# spi1_1.net
KiCad netlist of a schematic drawn in EAGLE
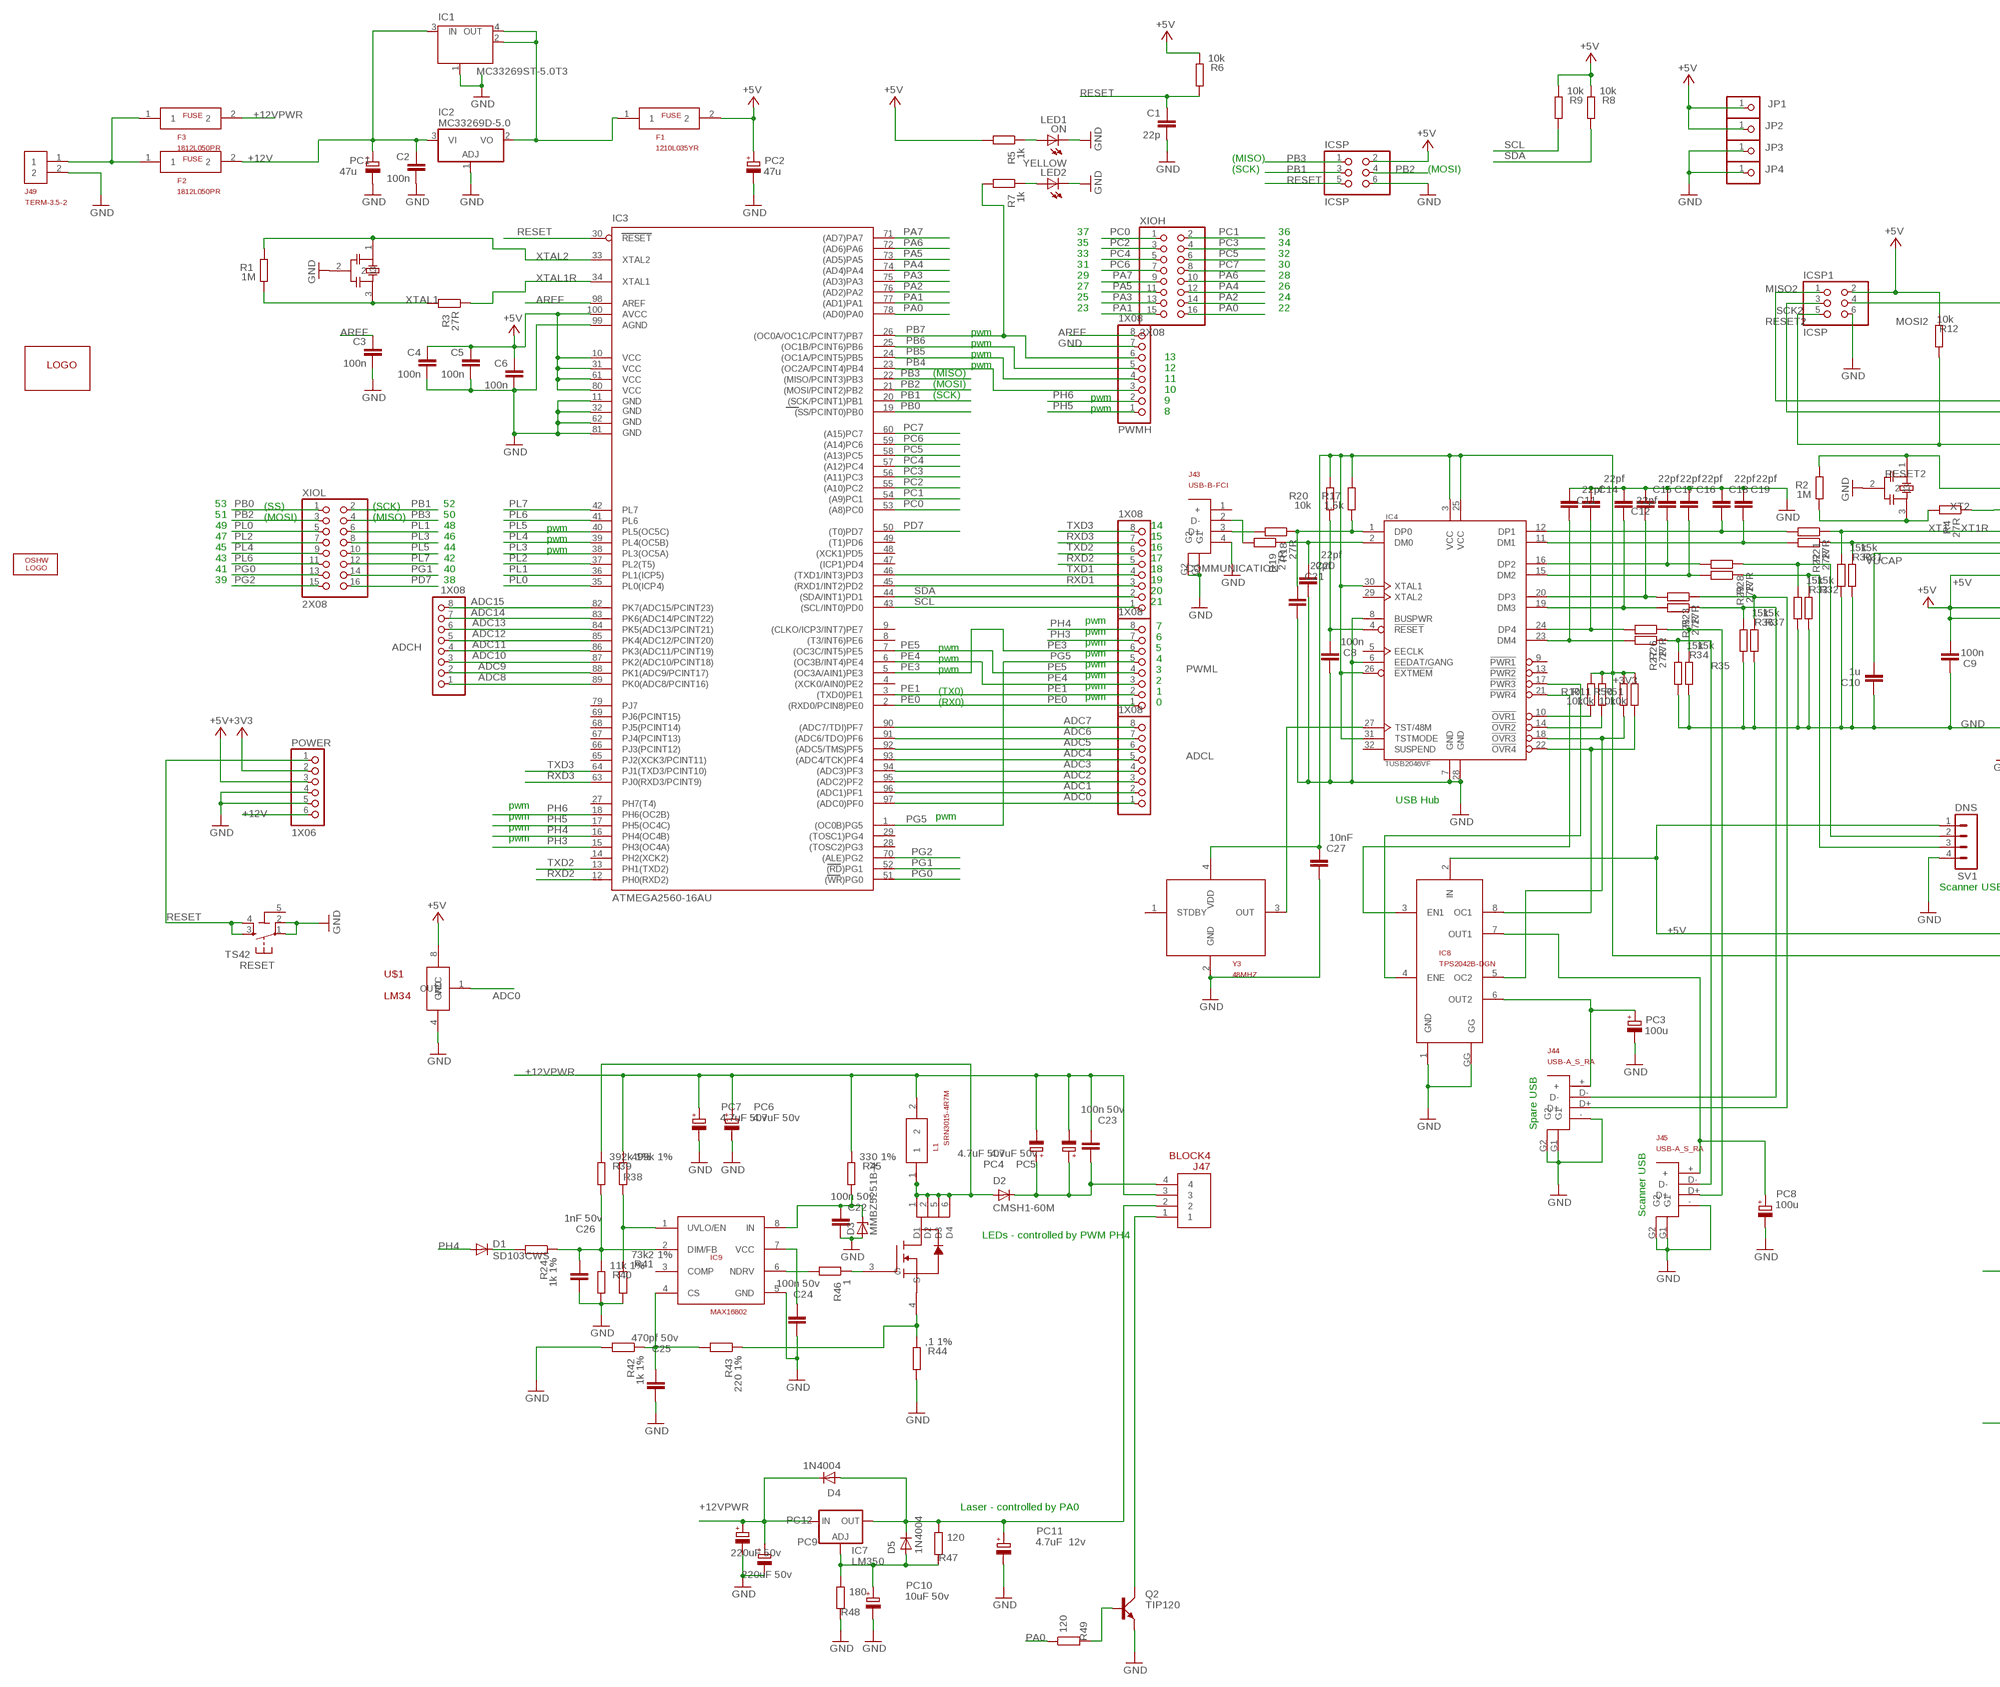
[diagram p0: schematic, sheet 1, part 1 of 2]
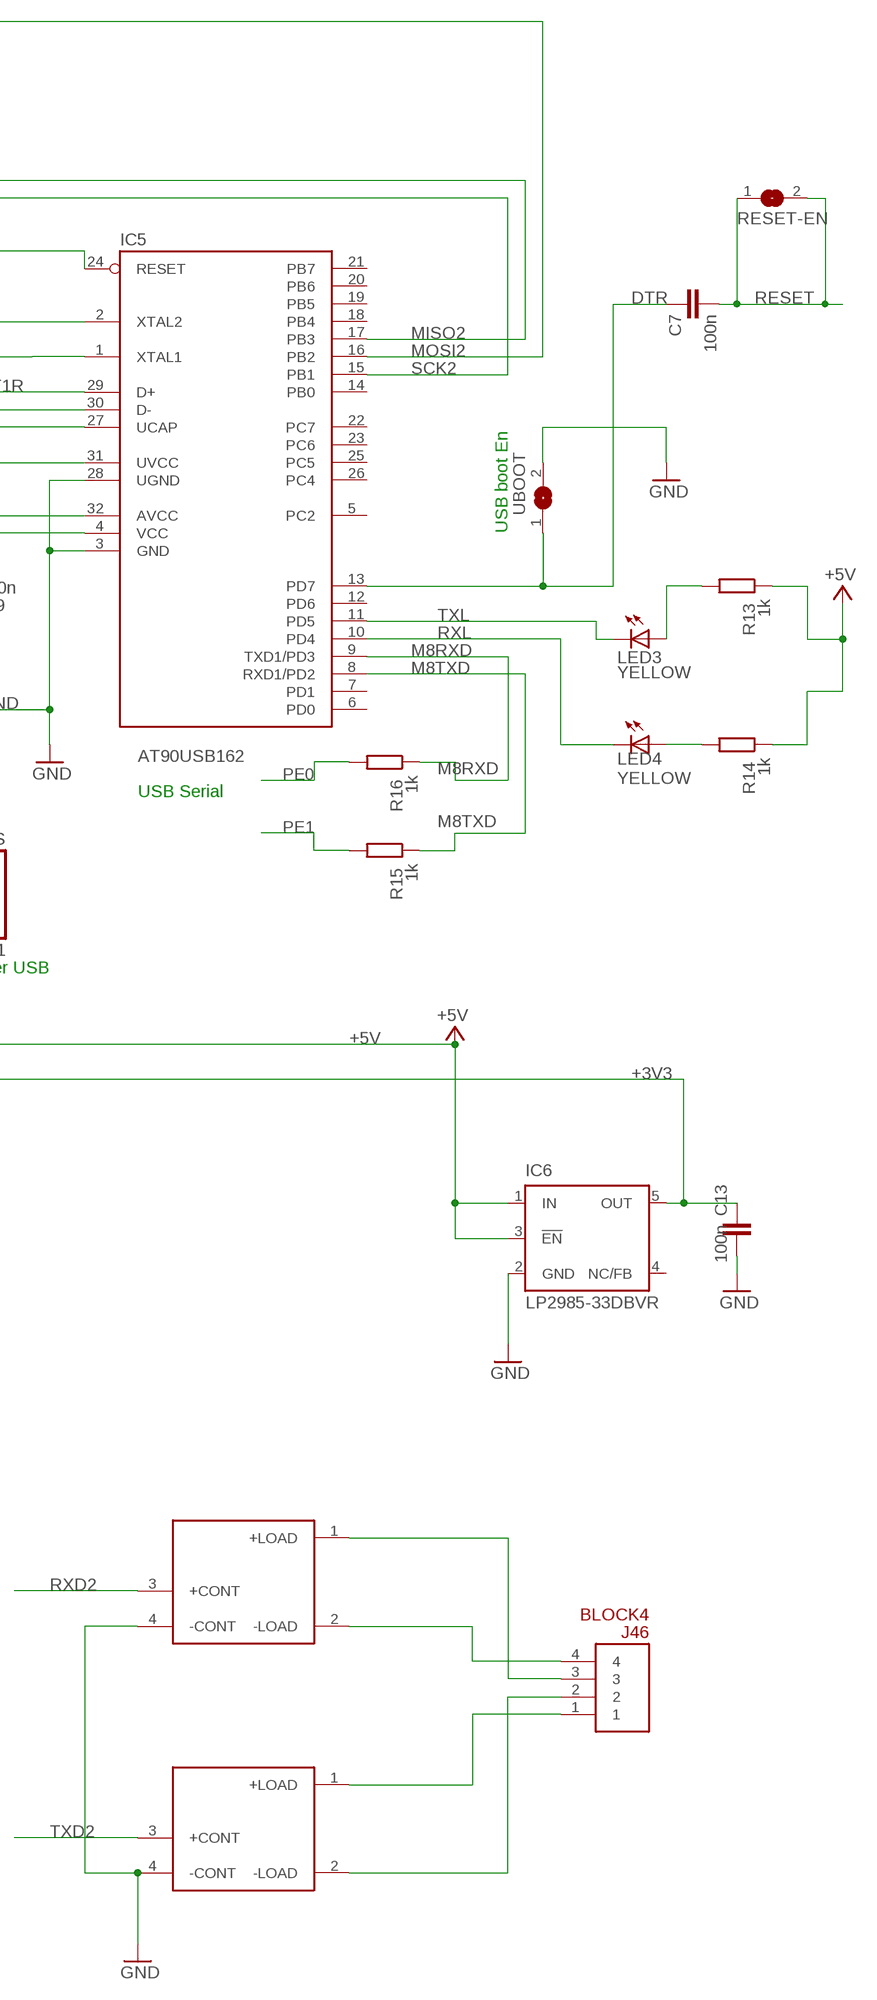
[diagram p1: schematic, sheet 1, part 2 of 2]

(export (version "E")
  (design (tool "Eeschema 10.0.6"))
  (components
    (comp (ref "ADCH")
      (value "1X08")
      (footprint "eagle-import:1X08")
      (libsource (lib "eagle-import") (part "PINHD-1X8"))
    )
    (comp (ref "ADCL")
      (value "1X08")
      (footprint "eagle-import:1X08")
      (libsource (lib "eagle-import") (part "PINHD-1X8"))
    )
    (comp (ref "C1")
      (value "22p")
      (footprint "eagle-import:C0603-ROUND")
      (libsource (lib "eagle-import") (part "C-EU0603-RND"))
    )
    (comp (ref "C2")
      (value "100n")
      (footprint "eagle-import:C0603-ROUND")
      (libsource (lib "eagle-import") (part "C-EU0603-RND"))
    )
    (comp (ref "C3")
      (value "100n")
      (footprint "eagle-import:C0603-ROUND")
      (libsource (lib "eagle-import") (part "C-EU0603-RND"))
    )
    (comp (ref "C4")
      (value "100n")
      (footprint "eagle-import:C0603-ROUND")
      (libsource (lib "eagle-import") (part "C-EU0603-RND"))
    )
    (comp (ref "C5")
      (value "100n")
      (footprint "eagle-import:C0603-ROUND")
      (libsource (lib "eagle-import") (part "C-EU0603-RND"))
    )
    (comp (ref "C6")
      (value "100n")
      (footprint "eagle-import:C0603-ROUND")
      (libsource (lib "eagle-import") (part "C-EU0603-RND"))
    )
    (comp (ref "C7")
      (value "100n")
      (footprint "eagle-import:C0603-ROUND")
      (libsource (lib "eagle-import") (part "C-EU0603-RND"))
    )
    (comp (ref "C8")
      (value "100n")
      (footprint "eagle-import:C0603-ROUND")
      (libsource (lib "eagle-import") (part "C-EU0603-RND"))
    )
    (comp (ref "C9")
      (value "100n")
      (footprint "eagle-import:C0603-ROUND")
      (libsource (lib "eagle-import") (part "C-EU0603-RND"))
    )
    (comp (ref "C10")
      (value "1u")
      (footprint "eagle-import:C0603-ROUND")
      (libsource (lib "eagle-import") (part "C-EU0603-RND"))
    )
    (comp (ref "C11")
      (value "22pf")
      (footprint "eagle-import:C0603-ROUND")
      (libsource (lib "eagle-import") (part "C-EU0603-RND"))
    )
    (comp (ref "C12")
      (value "22pf")
      (footprint "eagle-import:C0603-ROUND")
      (libsource (lib "eagle-import") (part "C-EU0603-RND"))
    )
    (comp (ref "C13")
      (value "100n")
      (footprint "eagle-import:C0603-ROUND")
      (libsource (lib "eagle-import") (part "C-EU0603-RND"))
    )
    (comp (ref "C14")
      (value "22pf")
      (footprint "eagle-import:C0603-ROUND")
      (libsource (lib "eagle-import") (part "C-EU0603-RND"))
    )
    (comp (ref "C15")
      (value "22pf")
      (footprint "eagle-import:C0603-ROUND")
      (libsource (lib "eagle-import") (part "C-EU0603-RND"))
    )
    (comp (ref "C16")
      (value "22pf")
      (footprint "eagle-import:C0603-ROUND")
      (libsource (lib "eagle-import") (part "C-EU0603-RND"))
    )
    (comp (ref "C17")
      (value "22pf")
      (footprint "eagle-import:C0603-ROUND")
      (libsource (lib "eagle-import") (part "C-EU0603-RND"))
    )
    (comp (ref "C18")
      (value "22pf")
      (footprint "eagle-import:C0603-ROUND")
      (libsource (lib "eagle-import") (part "C-EU0603-RND"))
    )
    (comp (ref "C19")
      (value "22pf")
      (footprint "eagle-import:C0603-ROUND")
      (libsource (lib "eagle-import") (part "C-EU0603-RND"))
    )
    (comp (ref "C20")
      (value "22pf")
      (footprint "eagle-import:C0603-ROUND")
      (libsource (lib "eagle-import") (part "C-EU0603-RND"))
    )
    (comp (ref "C21")
      (value "22pf")
      (footprint "eagle-import:C0603-ROUND")
      (libsource (lib "eagle-import") (part "C-EU0603-RND"))
    )
    (comp (ref "C22")
      (value "100n 50v")
      (footprint "eagle-import:C0603-ROUND")
      (libsource (lib "eagle-import") (part "C-EU0603-RND"))
    )
    (comp (ref "C23")
      (value "100n 50v")
      (footprint "eagle-import:C0603-ROUND")
      (libsource (lib "eagle-import") (part "C-EU0603-RND"))
    )
    (comp (ref "C24")
      (value "100n 50v")
      (footprint "eagle-import:C0603-ROUND")
      (libsource (lib "eagle-import") (part "C-EU0603-RND"))
    )
    (comp (ref "C25")
      (value "470pf 50v")
      (footprint "eagle-import:C0603-ROUND")
      (libsource (lib "eagle-import") (part "C-EU0603-RND"))
    )
    (comp (ref "C26")
      (value "1nF 50v")
      (footprint "eagle-import:C0603-ROUND")
      (libsource (lib "eagle-import") (part "C-EU0603-RND"))
    )
    (comp (ref "C27")
      (value "10nF")
      (footprint "eagle-import:C0603-ROUND")
      (libsource (lib "eagle-import") (part "C-EU0603-RND"))
    )
    (comp (ref "COMMUNICATION")
      (value "1X08")
      (footprint "eagle-import:1X08")
      (libsource (lib "eagle-import") (part "PINHD-1X8"))
    )
    (comp (ref "D1")
      (value "SD103CWS")
      (footprint "eagle-import:SOD323-W")
      (libsource (lib "eagle-import") (part "DIODE-SOD323-W"))
    )
    (comp (ref "D2")
      (value "CMSH1-60M")
      (footprint "eagle-import:SMA-DO214AC")
      (libsource (lib "eagle-import") (part "GF1"))
    )
    (comp (ref "D3")
      (value "MMBZ5251B-V")
      (footprint "eagle-import:SOT23")
      (libsource (lib "eagle-import") (part "ZENER-DIODESOT23"))
    )
    (comp (ref "D4")
      (value "1N4004")
      (footprint "eagle-import:SMA-DO214AC")
      (libsource (lib "eagle-import") (part "GF1"))
    )
    (comp (ref "D5")
      (value "1N4004")
      (footprint "eagle-import:SMA-DO214AC")
      (libsource (lib "eagle-import") (part "GF1"))
    )
    (comp (ref "F1")
      (value "1210L035YR")
      (footprint "eagle-import:POLY6")
      (libsource (lib "eagle-import") (part "1210L035YR"))
    )
    (comp (ref "F2")
      (value "1812L050PR")
      (footprint "eagle-import:POLY15")
      (libsource (lib "eagle-import") (part "1812L050PR"))
    )
    (comp (ref "F3")
      (value "1812L050PR")
      (footprint "eagle-import:POLY15")
      (libsource (lib "eagle-import") (part "1812L050PR"))
    )
    (comp (ref "IC1")
      (value "MC33269ST-5.0T3")
      (footprint "eagle-import:SOT223")
      (libsource (lib "eagle-import") (part "MC33269ST-3.3T3"))
    )
    (comp (ref "IC2")
      (value "MC33269D-5.0")
      (footprint "eagle-import:DPACK")
      (libsource (lib "eagle-import") (part "MC33269?D-5.0"))
    )
    (comp (ref "IC3")
      (value "ATMEGA2560-16AU")
      (footprint "eagle-import:TQFP100")
      (libsource (lib "eagle-import") (part "ATMEGAAU1280-16"))
    )
    (comp (ref "IC4")
      (value "TUSB2046VF")
      (footprint "eagle-import:TQFP32-08")
      (libsource (lib "eagle-import") (part "TUSB2046VF"))
    )
    (comp (ref "IC5")
      (value "AT90USB162")
      (footprint "eagle-import:TQFP32-08")
      (libsource (lib "eagle-import") (part "AT90USB162"))
    )
    (comp (ref "IC6")
      (value "LP2985-33DBVR")
      (footprint "eagle-import:SOT23-DBV")
      (fields (field (name "MF") "TEXAS INSTRUMENTS") (field (name "MPN") "TPS77033DBVT"))
      (libsource (lib "eagle-import") (part "TPS77033"))
    )
    (comp (ref "IC7")
      (value "LM350")
      (footprint "eagle-import:317TS")
      (libsource (lib "eagle-import") (part "LM317TS"))
    )
    (comp (ref "IC8")
      (value "TPS2042B-DGN")
      (footprint "eagle-import:DGN-8")
      (libsource (lib "eagle-import") (part "TPS2042B-DGN"))
    )
    (comp (ref "IC9")
      (value "MAX16802")
      (footprint "eagle-import:USOP-8")
      (libsource (lib "eagle-import") (part "MAX1602B"))
    )
    (comp (ref "ICSP")
      (value "ICSP")
      (footprint "eagle-import:2X03")
      (libsource (lib "eagle-import") (part "PINHD-2X3"))
    )
    (comp (ref "ICSP1")
      (value "ICSP")
      (footprint "eagle-import:2X03")
      (libsource (lib "eagle-import") (part "PINHD-2X3"))
    )
    (comp (ref "J43")
      (value "USB-B-FCI")
      (footprint "eagle-import:USB-B")
      (libsource (lib "eagle-import") (part "USB-B-FCI"))
    )
    (comp (ref "J44")
      (value "USB-A_S_RA")
      (footprint "eagle-import:USB-A")
      (libsource (lib "eagle-import") (part "USB-A_S_RA"))
    )
    (comp (ref "J45")
      (value "USB-A_S_RA")
      (footprint "eagle-import:USB-A")
      (libsource (lib "eagle-import") (part "USB-A_S_RA"))
    )
    (comp (ref "J46")
      (value "BLOCK4")
      (footprint "eagle-import:TERM3.5-4")
      (libsource (lib "eagle-import") (part "BLOCK4"))
    )
    (comp (ref "J47")
      (value "BLOCK4")
      (footprint "eagle-import:TERM3.5-4")
      (libsource (lib "eagle-import") (part "BLOCK4"))
    )
    (comp (ref "J49")
      (value "TERM-3.5-2")
      (footprint "eagle-import:TERM3.5-2")
      (libsource (lib "eagle-import") (part "TERM-3.5-2"))
    )
    (comp (ref "JP1")
      (value "PINHD-1X1")
      (footprint "eagle-import:1X01")
      (libsource (lib "eagle-import") (part "PINHD-1X1"))
    )
    (comp (ref "JP2")
      (value "PINHD-1X1")
      (footprint "eagle-import:1X01")
      (libsource (lib "eagle-import") (part "PINHD-1X1"))
    )
    (comp (ref "JP3")
      (value "PINHD-1X1")
      (footprint "eagle-import:1X01")
      (libsource (lib "eagle-import") (part "PINHD-1X1"))
    )
    (comp (ref "JP4")
      (value "PINHD-1X1")
      (footprint "eagle-import:1X01")
      (libsource (lib "eagle-import") (part "PINHD-1X1"))
    )
    (comp (ref "L1")
      (value "SRN3015-4R7M")
      (footprint "eagle-import:INDUCT1")
      (libsource (lib "eagle-import") (part "INDUCT1"))
    )
    (comp (ref "LED2")
      (value "YELLOW")
      (footprint "eagle-import:CHIP-LED0805")
      (libsource (lib "eagle-import") (part "LEDCHIP-LED0805"))
    )
    (comp (ref "LED3")
      (value "YELLOW")
      (footprint "eagle-import:CHIP-LED0805")
      (libsource (lib "eagle-import") (part "LEDCHIP-LED0805"))
    )
    (comp (ref "LED4")
      (value "YELLOW")
      (footprint "eagle-import:CHIP-LED0805")
      (libsource (lib "eagle-import") (part "LEDCHIP-LED0805"))
    )
    (comp (ref "LOGO2")
      (value "OSHW_LOGO_FILLX0350-NT")
      (footprint "eagle-import:OSHW_FILLX350_NOTEXT")
      (libsource (lib "eagle-import") (part "OSHW_LOGO_FILLX0350-NT"))
    )
    (comp (ref "ON")
      (value "LED1")
      (footprint "eagle-import:CHIP-LED0805")
      (libsource (lib "eagle-import") (part "LEDCHIP-LED0805"))
    )
    (comp (ref "PC1")
      (value "47u")
      (footprint "eagle-import:UD-6,3X7,7_NICHICON")
      (libsource (lib "eagle-import") (part "CPOL-EUUD-6,3X7,7"))
    )
    (comp (ref "PC2")
      (value "47u")
      (footprint "eagle-import:UD-6,3X7,7_NICHICON")
      (libsource (lib "eagle-import") (part "CPOL-EUUD-6,3X7,7"))
    )
    (comp (ref "PC3")
      (value "100u")
      (footprint "eagle-import:UD-6,3X7,7_NICHICON")
      (libsource (lib "eagle-import") (part "CPOL-EUUD-6,3X7,7"))
    )
    (comp (ref "PC4")
      (value "4.7uF 50v")
      (footprint "eagle-import:PANASONIC_C")
      (libsource (lib "eagle-import") (part "CPOL-EUC"))
    )
    (comp (ref "PC5")
      (value "4.7uF 50v")
      (footprint "eagle-import:PANASONIC_C")
      (libsource (lib "eagle-import") (part "CPOL-EUC"))
    )
    (comp (ref "PC6")
      (value "4.7uF 50v")
      (footprint "eagle-import:PANASONIC_C")
      (libsource (lib "eagle-import") (part "CPOL-EUC"))
    )
    (comp (ref "PC7")
      (value "4.7uF 50v")
      (footprint "eagle-import:PANASONIC_C")
      (libsource (lib "eagle-import") (part "CPOL-EUC"))
    )
    (comp (ref "PC8")
      (value "100u")
      (footprint "eagle-import:UD-6,3X7,7_NICHICON")
      (libsource (lib "eagle-import") (part "CPOL-EUUD-6,3X7,7"))
    )
    (comp (ref "PC9")
      (value "220uF 50v")
      (footprint "eagle-import:PANASONIC_G")
      (libsource (lib "eagle-import") (part "CPOL-EUG"))
    )
    (comp (ref "PC10")
      (value "10uF 50v")
      (footprint "eagle-import:PANASONIC_D")
      (libsource (lib "eagle-import") (part "CPOL-EUD"))
    )
    (comp (ref "PC11")
      (value "4.7uF 12v")
      (footprint "eagle-import:PANASONIC_C")
      (libsource (lib "eagle-import") (part "CPOL-EUC"))
    )
    (comp (ref "PC12")
      (value "220uF 50v")
      (footprint "eagle-import:PANASONIC_G")
      (libsource (lib "eagle-import") (part "CPOL-EUG"))
    )
    (comp (ref "POWER")
      (value "1X06")
      (footprint "eagle-import:1X06")
      (libsource (lib "eagle-import") (part "PINHD-1X6"))
    )
    (comp (ref "PWMH")
      (value "1X08")
      (footprint "eagle-import:1X08")
      (libsource (lib "eagle-import") (part "PINHD-1X8"))
    )
    (comp (ref "PWML")
      (value "1X08")
      (footprint "eagle-import:1X08")
      (libsource (lib "eagle-import") (part "PINHD-1X8"))
    )
    (comp (ref "Q2")
      (value "TIP120")
      (footprint "eagle-import:TO220AV")
      (libsource (lib "eagle-import") (part "TIP41C"))
    )
    (comp (ref "R1")
      (value "1M")
      (footprint "eagle-import:R0603-ROUND")
      (libsource (lib "eagle-import") (part "R-EU_R0603"))
    )
    (comp (ref "R2")
      (value "1M")
      (footprint "eagle-import:R0603-ROUND")
      (libsource (lib "eagle-import") (part "R-EU_R0603"))
    )
    (comp (ref "R3")
      (value "27R")
      (footprint "eagle-import:R0603-ROUND")
      (libsource (lib "eagle-import") (part "R-EU_R0603"))
    )
    (comp (ref "R4")
      (value "27R")
      (footprint "eagle-import:R0603-ROUND")
      (libsource (lib "eagle-import") (part "R-EU_R0603"))
    )
    (comp (ref "R5")
      (value "1k")
      (footprint "eagle-import:R0603-ROUND")
      (libsource (lib "eagle-import") (part "R-EU_R0603"))
    )
    (comp (ref "R6")
      (value "10k")
      (footprint "eagle-import:R0603-ROUND")
      (libsource (lib "eagle-import") (part "R-EU_R0603"))
    )
    (comp (ref "R7")
      (value "1k")
      (footprint "eagle-import:R0603-ROUND")
      (libsource (lib "eagle-import") (part "R-EU_R0603"))
    )
    (comp (ref "R8")
      (value "10k")
      (footprint "eagle-import:R0603-ROUND")
      (libsource (lib "eagle-import") (part "R-EU_R0603"))
    )
    (comp (ref "R9")
      (value "10k")
      (footprint "eagle-import:R0603-ROUND")
      (libsource (lib "eagle-import") (part "R-EU_R0603"))
    )
    (comp (ref "R10")
      (value "10k")
      (footprint "eagle-import:R0603-ROUND")
      (libsource (lib "eagle-import") (part "R-EU_R0603"))
    )
    (comp (ref "R11")
      (value "10k")
      (footprint "eagle-import:R0603-ROUND")
      (libsource (lib "eagle-import") (part "R-EU_R0603"))
    )
    (comp (ref "R12")
      (value "10k")
      (footprint "eagle-import:R0603-ROUND")
      (libsource (lib "eagle-import") (part "R-EU_R0603"))
    )
    (comp (ref "R13")
      (value "1k")
      (footprint "eagle-import:R0603-ROUND")
      (libsource (lib "eagle-import") (part "R-EU_R0603"))
    )
    (comp (ref "R14")
      (value "1k")
      (footprint "eagle-import:R0603-ROUND")
      (libsource (lib "eagle-import") (part "R-EU_R0603"))
    )
    (comp (ref "R15")
      (value "1k")
      (footprint "eagle-import:R0603-ROUND")
      (libsource (lib "eagle-import") (part "R-EU_R0603"))
    )
    (comp (ref "R16")
      (value "1k")
      (footprint "eagle-import:R0603-ROUND")
      (libsource (lib "eagle-import") (part "R-EU_R0603"))
    )
    (comp (ref "R17")
      (value "1.5k")
      (footprint "eagle-import:R0603-ROUND")
      (libsource (lib "eagle-import") (part "R-EU_R0603"))
    )
    (comp (ref "R18")
      (value "27R")
      (footprint "eagle-import:R0603-ROUND")
      (libsource (lib "eagle-import") (part "R-EU_R0603"))
    )
    (comp (ref "R19")
      (value "27R")
      (footprint "eagle-import:R0603-ROUND")
      (libsource (lib "eagle-import") (part "R-EU_R0603"))
    )
    (comp (ref "R20")
      (value "10k")
      (footprint "eagle-import:R0603-ROUND")
      (libsource (lib "eagle-import") (part "R-EU_R0603"))
    )
    (comp (ref "R21")
      (value "27R")
      (footprint "eagle-import:R0603-ROUND")
      (libsource (lib "eagle-import") (part "R-EU_R0603"))
    )
    (comp (ref "R22")
      (value "27R")
      (footprint "eagle-import:R0603-ROUND")
      (libsource (lib "eagle-import") (part "R-EU_R0603"))
    )
    (comp (ref "R23")
      (value "27R")
      (footprint "eagle-import:R0603-ROUND")
      (libsource (lib "eagle-import") (part "R-EU_R0603"))
    )
    (comp (ref "R24")
      (value "1k 1%")
      (footprint "eagle-import:R0603-ROUND")
      (libsource (lib "eagle-import") (part "R-EU_R0603"))
    )
    (comp (ref "R25")
      (value "27R")
      (footprint "eagle-import:R0603-ROUND")
      (libsource (lib "eagle-import") (part "R-EU_R0603"))
    )
    (comp (ref "R26")
      (value "27R")
      (footprint "eagle-import:R0603-ROUND")
      (libsource (lib "eagle-import") (part "R-EU_R0603"))
    )
    (comp (ref "R27")
      (value "27R")
      (footprint "eagle-import:R0603-ROUND")
      (libsource (lib "eagle-import") (part "R-EU_R0603"))
    )
    (comp (ref "R28")
      (value "27R")
      (footprint "eagle-import:R0603-ROUND")
      (libsource (lib "eagle-import") (part "R-EU_R0603"))
    )
    (comp (ref "R29")
      (value "27R")
      (footprint "eagle-import:R0603-ROUND")
      (libsource (lib "eagle-import") (part "R-EU_R0603"))
    )
    (comp (ref "R30")
      (value "15k")
      (footprint "eagle-import:R0603-ROUND")
      (libsource (lib "eagle-import") (part "R-EU_R0603"))
    )
    (comp (ref "R31")
      (value "15k")
      (footprint "eagle-import:R0603-ROUND")
      (libsource (lib "eagle-import") (part "R-EU_R0603"))
    )
    (comp (ref "R32")
      (value "15k")
      (footprint "eagle-import:R0603-ROUND")
      (libsource (lib "eagle-import") (part "R-EU_R0603"))
    )
    (comp (ref "R33")
      (value "15k")
      (footprint "eagle-import:R0603-ROUND")
      (libsource (lib "eagle-import") (part "R-EU_R0603"))
    )
    (comp (ref "R34")
      (value "15k")
      (footprint "eagle-import:R0603-ROUND")
      (libsource (lib "eagle-import") (part "R-EU_R0603"))
    )
    (comp (ref "R35")
      (value "15k")
      (footprint "eagle-import:R0603-ROUND")
      (libsource (lib "eagle-import") (part "R-EU_R0603"))
    )
    (comp (ref "R36")
      (value "15k")
      (footprint "eagle-import:R0603-ROUND")
      (libsource (lib "eagle-import") (part "R-EU_R0603"))
    )
    (comp (ref "R37")
      (value "15k")
      (footprint "eagle-import:R0603-ROUND")
      (libsource (lib "eagle-import") (part "R-EU_R0603"))
    )
    (comp (ref "R38")
      (value "499k 1%")
      (footprint "eagle-import:R0603-ROUND")
      (libsource (lib "eagle-import") (part "R-EU_R0603"))
    )
    (comp (ref "R39")
      (value "392k 1%")
      (footprint "eagle-import:R0603-ROUND")
      (libsource (lib "eagle-import") (part "R-EU_R0603"))
    )
    (comp (ref "R40")
      (value "11k 1%")
      (footprint "eagle-import:R0603-ROUND")
      (libsource (lib "eagle-import") (part "R-EU_R0603"))
    )
    (comp (ref "R41")
      (value "73k2 1%")
      (footprint "eagle-import:R0603-ROUND")
      (libsource (lib "eagle-import") (part "R-EU_R0603"))
    )
    (comp (ref "R42")
      (value "1k 1%")
      (footprint "eagle-import:R0603-ROUND")
      (libsource (lib "eagle-import") (part "R-EU_R0603"))
    )
    (comp (ref "R43")
      (value "220 1%")
      (footprint "eagle-import:R0603-ROUND")
      (libsource (lib "eagle-import") (part "R-EU_R0603"))
    )
    (comp (ref "R44")
      (value ",1 1%")
      (footprint "eagle-import:R1206")
      (libsource (lib "eagle-import") (part "R-EU_R1206"))
    )
    (comp (ref "R45")
      (value "330 1%")
      (footprint "eagle-import:R1206")
      (libsource (lib "eagle-import") (part "R-EU_R1206"))
    )
    (comp (ref "R46")
      (value "1")
      (footprint "eagle-import:R0603-ROUND")
      (libsource (lib "eagle-import") (part "R-EU_R0603"))
    )
    (comp (ref "R47")
      (value "120")
      (footprint "eagle-import:R0603-ROUND")
      (libsource (lib "eagle-import") (part "R-EU_R0603"))
    )
    (comp (ref "R48")
      (value "180")
      (footprint "eagle-import:R0603-ROUND")
      (libsource (lib "eagle-import") (part "R-EU_R0603"))
    )
    (comp (ref "R49")
      (value "120")
      (footprint "eagle-import:R0603-ROUND")
      (libsource (lib "eagle-import") (part "R-EU_R0603"))
    )
    (comp (ref "R50")
      (value "10k")
      (footprint "eagle-import:R0603-ROUND")
      (libsource (lib "eagle-import") (part "R-EU_R0603"))
    )
    (comp (ref "R51")
      (value "10k")
      (footprint "eagle-import:R0603-ROUND")
      (libsource (lib "eagle-import") (part "R-EU_R0603"))
    )
    (comp (ref "RELAY1")
      (value "XRELAY")
      (footprint "eagle-import:XRELAY")
      (libsource (lib "eagle-import") (part "XRELAY"))
    )
    (comp (ref "RELAY2")
      (value "XRELAY")
      (footprint "eagle-import:XRELAY")
      (libsource (lib "eagle-import") (part "XRELAY"))
    )
    (comp (ref "RESET")
      (value "TS42")
      (footprint "eagle-import:TS42")
      (libsource (lib "eagle-import") (part "TS42"))
    )
    (comp (ref "RESET-EN")
      (value "SJ")
      (footprint "eagle-import:SJ")
      (libsource (lib "eagle-import") (part "SJ"))
    )
    (comp (ref "SV1")
      (value "DNS")
      (footprint "eagle-import:MA04-1")
      (libsource (lib "eagle-import") (part "MA04-1"))
    )
    (comp (ref "U$1")
      (value "LM34")
      (footprint "eagle-import:SS08")
      (libsource (lib "eagle-import") (part "LM34"))
    )
    (comp (ref "U$6")
      (value "SI3458DVB")
      (footprint "eagle-import:TSOP6")
      (libsource (lib "eagle-import") (part "SI3458DVB"))
    )
    (comp (ref "U$15")
      (value "LOGO")
      (footprint "eagle-import:LOGO")
      (libsource (lib "eagle-import") (part "LOGO"))
    )
    (comp (ref "UBOOT")
      (value "SJ")
      (footprint "eagle-import:SJ")
      (libsource (lib "eagle-import") (part "SJ"))
    )
    (comp (ref "XIOH")
      (value "2X08")
      (footprint "eagle-import:2X08")
      (libsource (lib "eagle-import") (part "PINHD-2X8"))
    )
    (comp (ref "XIOL")
      (value "2X08")
      (footprint "eagle-import:2X08")
      (libsource (lib "eagle-import") (part "PINHD-2X8"))
    )
    (comp (ref "Y1")
      (value "AWSCR")
      (footprint "eagle-import:RESONATOR1")
      (libsource (lib "eagle-import") (part "AWSCR"))
    )
    (comp (ref "Y2")
      (value "AWSCR")
      (footprint "eagle-import:RESONATOR1")
      (libsource (lib "eagle-import") (part "AWSCR"))
    )
    (comp (ref "Y3")
      (value "48MHZ")
      (footprint "eagle-import:XTAL1")
      (libsource (lib "eagle-import") (part "XTAL1"))
    )
  )
  (nets
    (net (code "1") (name "+3V3") (class "Default")
      (node (ref "C13") (pin "2") (pinfunction "2_2") (pintype "passive"))
      (node (ref "C27") (pin "1") (pinfunction "1_1") (pintype "passive"))
      (node (ref "IC4") (pin "25") (pinfunction "VCC_25") (pintype "power_in"))
      (node (ref "IC4") (pin "26") (pinfunction "~{EXTMEM}_26") (pintype "bidirectional"))
      (node (ref "IC4") (pin "3") (pinfunction "VCC_3") (pintype "power_in"))
      (node (ref "IC4") (pin "30") (pinfunction "XTAL1_30") (pintype "bidirectional"))
      (node (ref "IC4") (pin "31") (pinfunction "TSTMODE_31") (pintype "input"))
      (node (ref "IC6") (pin "5") (pinfunction "OUT_5") (pintype "passive"))
      (node (ref "POWER") (pin "2") (pinfunction "2_2") (pintype "passive"))
      (node (ref "R10") (pin "2") (pinfunction "2_2") (pintype "passive"))
      (node (ref "R11") (pin "2") (pinfunction "2_2") (pintype "passive"))
      (node (ref "R17") (pin "2") (pinfunction "2_2") (pintype "passive"))
      (node (ref "R20") (pin "2") (pinfunction "2_2") (pintype "passive"))
      (node (ref "R50") (pin "2") (pinfunction "2_2") (pintype "passive"))
      (node (ref "R51") (pin "2") (pinfunction "2_2") (pintype "passive"))
      (node (ref "Y3") (pin "4") (pinfunction "VDD_4") (pintype "bidirectional"))
    )
    (net (code "2") (name "+5V") (class "Default")
      (node (ref "C4") (pin "1") (pinfunction "1_1") (pintype "passive"))
      (node (ref "C5") (pin "1") (pinfunction "1_1") (pintype "passive"))
      (node (ref "C6") (pin "1") (pinfunction "1_1") (pintype "passive"))
      (node (ref "C9") (pin "1") (pinfunction "1_1") (pintype "passive"))
      (node (ref "F1") (pin "2") (pinfunction "2_2") (pintype "bidirectional"))
      (node (ref "IC3") (pin "10") (pinfunction "VCC_10") (pintype "power_in"))
      (node (ref "IC3") (pin "100") (pinfunction "AVCC_100") (pintype "power_in"))
      (node (ref "IC3") (pin "31") (pinfunction "VCC1_31") (pintype "power_in"))
      (node (ref "IC3") (pin "61") (pinfunction "VCC2_61") (pintype "power_in"))
      (node (ref "IC3") (pin "80") (pinfunction "VCC3_80") (pintype "power_in"))
      (node (ref "IC5") (pin "31") (pinfunction "UVCC_31") (pintype "power_in"))
      (node (ref "IC5") (pin "32") (pinfunction "AVCC_32") (pintype "bidirectional"))
      (node (ref "IC5") (pin "4") (pinfunction "VCC_4") (pintype "bidirectional"))
      (node (ref "IC6") (pin "1") (pinfunction "IN_1") (pintype "input"))
      (node (ref "IC6") (pin "3") (pinfunction "~{EN}_3") (pintype "input"))
      (node (ref "IC8") (pin "2") (pinfunction "IN_2") (pintype "bidirectional"))
      (node (ref "ICSP") (pin "2") (pinfunction "2_2") (pintype "passive"))
      (node (ref "ICSP1") (pin "2") (pinfunction "2_2") (pintype "passive"))
      (node (ref "JP1") (pin "1") (pinfunction "1_1") (pintype "passive"))
      (node (ref "JP2") (pin "1") (pinfunction "1_1") (pintype "passive"))
      (node (ref "PC2") (pin "+") (pinfunction "+_+") (pintype "passive"))
      (node (ref "POWER") (pin "3") (pinfunction "3_3") (pintype "passive"))
      (node (ref "R12") (pin "1") (pinfunction "1_1") (pintype "passive"))
      (node (ref "R13") (pin "1") (pinfunction "1_1") (pintype "passive"))
      (node (ref "R14") (pin "1") (pinfunction "1_1") (pintype "passive"))
      (node (ref "R5") (pin "2") (pinfunction "2_2") (pintype "passive"))
      (node (ref "R6") (pin "1") (pinfunction "1_1") (pintype "passive"))
      (node (ref "R8") (pin "1") (pinfunction "1_1") (pintype "passive"))
      (node (ref "R9") (pin "1") (pinfunction "1_1") (pintype "passive"))
      (node (ref "SV1") (pin "1") (pinfunction "1_1") (pintype "passive"))
      (node (ref "U$1") (pin "8") (pinfunction "VCC_8") (pintype "bidirectional"))
    )
    (net (code "3") (name "/+12V") (class "Default")
      (node (ref "C2") (pin "1") (pinfunction "1_1") (pintype "passive"))
      (node (ref "F2") (pin "2") (pinfunction "2_2") (pintype "bidirectional"))
      (node (ref "IC1") (pin "3") (pinfunction "IN_3") (pintype "input"))
      (node (ref "IC2") (pin "3") (pinfunction "VI_3") (pintype "input"))
      (node (ref "PC1") (pin "+") (pinfunction "+_+") (pintype "passive"))
      (node (ref "POWER") (pin "6") (pinfunction "6_6") (pintype "passive"))
    )
    (net (code "4") (name "/+12VPWR") (class "Default")
      (node (ref "C23") (pin "1") (pinfunction "1_1") (pintype "passive"))
      (node (ref "D4") (pin "K") (pinfunction "C_K") (pintype "passive"))
      (node (ref "F3") (pin "2") (pinfunction "2_2") (pintype "bidirectional"))
      (node (ref "IC7") (pin "3") (pinfunction "IN_3") (pintype "input"))
      (node (ref "J47") (pin "3") (pinfunction "3_3") (pintype "bidirectional"))
      (node (ref "L1") (pin "2") (pinfunction "2_2") (pintype "bidirectional"))
      (node (ref "PC12") (pin "+") (pinfunction "+_+") (pintype "passive"))
      (node (ref "PC4") (pin "-") (pinfunction "-_-") (pintype "passive"))
      (node (ref "PC5") (pin "-") (pinfunction "-_-") (pintype "passive"))
      (node (ref "PC6") (pin "+") (pinfunction "+_+") (pintype "passive"))
      (node (ref "PC7") (pin "+") (pinfunction "+_+") (pintype "passive"))
      (node (ref "PC9") (pin "+") (pinfunction "+_+") (pintype "passive"))
      (node (ref "R38") (pin "1") (pinfunction "1_1") (pintype "passive"))
      (node (ref "R45") (pin "1") (pinfunction "1_1") (pintype "passive"))
    )
    (net (code "5") (name "/5-GND") (class "Default")
      (node (ref "RESET") (pin "5") (pinfunction "5-GND_5") (pintype "power_in"))
    )
    (net (code "6") (name "/ADC0") (class "Default")
      (node (ref "ADCL") (pin "1") (pinfunction "1_1") (pintype "passive"))
      (node (ref "IC3") (pin "97") (pinfunction "(ADC0)PF0_97") (pintype "bidirectional"))
      (node (ref "U$1") (pin "1") (pinfunction "OUT_1") (pintype "bidirectional"))
    )
    (net (code "7") (name "/ADC1") (class "Default")
      (node (ref "ADCL") (pin "2") (pinfunction "2_2") (pintype "passive"))
      (node (ref "IC3") (pin "96") (pinfunction "(ADC1)PF1_96") (pintype "bidirectional"))
    )
    (net (code "8") (name "/ADC2") (class "Default")
      (node (ref "ADCL") (pin "3") (pinfunction "3_3") (pintype "passive"))
      (node (ref "IC3") (pin "95") (pinfunction "(ADC2)PF2_95") (pintype "bidirectional"))
    )
    (net (code "9") (name "/ADC3") (class "Default")
      (node (ref "ADCL") (pin "4") (pinfunction "4_4") (pintype "passive"))
      (node (ref "IC3") (pin "94") (pinfunction "(ADC3)PF3_94") (pintype "bidirectional"))
    )
    (net (code "10") (name "/ADC4") (class "Default")
      (node (ref "ADCL") (pin "5") (pinfunction "5_5") (pintype "passive"))
      (node (ref "IC3") (pin "93") (pinfunction "(ADC4/TCK)PF4_93") (pintype "bidirectional"))
    )
    (net (code "11") (name "/ADC5") (class "Default")
      (node (ref "ADCL") (pin "6") (pinfunction "6_6") (pintype "passive"))
      (node (ref "IC3") (pin "92") (pinfunction "(ADC5/TMS)PF5_92") (pintype "bidirectional"))
    )
    (net (code "12") (name "/ADC6") (class "Default")
      (node (ref "ADCL") (pin "7") (pinfunction "7_7") (pintype "passive"))
      (node (ref "IC3") (pin "91") (pinfunction "(ADC6/TDO)PF6_91") (pintype "bidirectional"))
    )
    (net (code "13") (name "/ADC7") (class "Default")
      (node (ref "ADCL") (pin "8") (pinfunction "8_8") (pintype "passive"))
      (node (ref "IC3") (pin "90") (pinfunction "(ADC7/TDI)PF7_90") (pintype "bidirectional"))
    )
    (net (code "14") (name "/ADC8") (class "Default")
      (node (ref "ADCH") (pin "1") (pinfunction "1_1") (pintype "passive"))
      (node (ref "IC3") (pin "89") (pinfunction "PK0(ADC8/PCINT16)_89") (pintype "bidirectional"))
    )
    (net (code "15") (name "/ADC9") (class "Default")
      (node (ref "ADCH") (pin "2") (pinfunction "2_2") (pintype "passive"))
      (node (ref "IC3") (pin "88") (pinfunction "PK1(ADC9/PCINT17)_88") (pintype "bidirectional"))
    )
    (net (code "16") (name "/ADC10") (class "Default")
      (node (ref "ADCH") (pin "3") (pinfunction "3_3") (pintype "passive"))
      (node (ref "IC3") (pin "87") (pinfunction "PK2(ADC10/PCINT18)_87") (pintype "bidirectional"))
    )
    (net (code "17") (name "/ADC11") (class "Default")
      (node (ref "ADCH") (pin "4") (pinfunction "4_4") (pintype "passive"))
      (node (ref "IC3") (pin "86") (pinfunction "PK3(ADC11/PCINT19)_86") (pintype "bidirectional"))
    )
    (net (code "18") (name "/ADC12") (class "Default")
      (node (ref "ADCH") (pin "5") (pinfunction "5_5") (pintype "passive"))
      (node (ref "IC3") (pin "85") (pinfunction "PK4(ADC12/PCINT20)_85") (pintype "bidirectional"))
    )
    (net (code "19") (name "/ADC13") (class "Default")
      (node (ref "ADCH") (pin "6") (pinfunction "6_6") (pintype "passive"))
      (node (ref "IC3") (pin "84") (pinfunction "PK5(ADC13/PCINT21)_84") (pintype "bidirectional"))
    )
    (net (code "20") (name "/ADC14") (class "Default")
      (node (ref "ADCH") (pin "7") (pinfunction "7_7") (pintype "passive"))
      (node (ref "IC3") (pin "83") (pinfunction "PK6(ADC14/PCINT22)_83") (pintype "bidirectional"))
    )
    (net (code "21") (name "/ADC15") (class "Default")
      (node (ref "ADCH") (pin "8") (pinfunction "8_8") (pintype "passive"))
      (node (ref "IC3") (pin "82") (pinfunction "PK7(ADC15/PCINT23)_82") (pintype "bidirectional"))
    )
    (net (code "22") (name "/AREF") (class "Default")
      (node (ref "C3") (pin "1") (pinfunction "1_1") (pintype "passive"))
      (node (ref "IC3") (pin "98") (pinfunction "AREF_98") (pintype "bidirectional"))
      (node (ref "PWMH") (pin "8") (pinfunction "8_8") (pintype "passive"))
    )
    (net (code "23") (name "/DTR") (class "Default")
      (node (ref "C7") (pin "1") (pinfunction "1_1") (pintype "passive"))
      (node (ref "IC5") (pin "13") (pinfunction "PD7_13") (pintype "bidirectional"))
      (node (ref "UBOOT") (pin "1") (pinfunction "1_1") (pintype "passive"))
    )
    (net (code "24") (name "/M8RXD") (class "Default")
      (node (ref "IC5") (pin "9") (pinfunction "TXD1/PD3_9") (pintype "bidirectional"))
      (node (ref "R16") (pin "1") (pinfunction "1_1") (pintype "passive"))
    )
    (net (code "25") (name "/M8TXD") (class "Default")
      (node (ref "IC5") (pin "8") (pinfunction "RXD1/PD2_8") (pintype "bidirectional"))
      (node (ref "R15") (pin "1") (pinfunction "1_1") (pintype "passive"))
    )
    (net (code "26") (name "/MISO2") (class "Default")
      (node (ref "IC5") (pin "17") (pinfunction "PB3_17") (pintype "bidirectional"))
      (node (ref "ICSP1") (pin "1") (pinfunction "1_1") (pintype "passive"))
    )
    (net (code "27") (name "/MOSI2") (class "Default")
      (node (ref "IC5") (pin "16") (pinfunction "PB2_16") (pintype "bidirectional"))
      (node (ref "ICSP1") (pin "4") (pinfunction "4_4") (pintype "passive"))
    )
    (net (code "28") (name "/PA0") (class "Default")
      (node (ref "IC3") (pin "78") (pinfunction "(AD0)PA0_78") (pintype "bidirectional"))
      (node (ref "R49") (pin "1") (pinfunction "1_1") (pintype "passive"))
      (node (ref "XIOH") (pin "16") (pinfunction "16_16") (pintype "passive"))
    )
    (net (code "29") (name "/PA1") (class "Default")
      (node (ref "IC3") (pin "77") (pinfunction "(AD1)PA1_77") (pintype "bidirectional"))
      (node (ref "XIOH") (pin "15") (pinfunction "15_15") (pintype "passive"))
    )
    (net (code "30") (name "/PA2") (class "Default")
      (node (ref "IC3") (pin "76") (pinfunction "(AD2)PA2_76") (pintype "bidirectional"))
      (node (ref "XIOH") (pin "14") (pinfunction "14_14") (pintype "passive"))
    )
    (net (code "31") (name "/PA3") (class "Default")
      (node (ref "IC3") (pin "75") (pinfunction "(AD3)PA3_75") (pintype "bidirectional"))
      (node (ref "XIOH") (pin "13") (pinfunction "13_13") (pintype "passive"))
    )
    (net (code "32") (name "/PA4") (class "Default")
      (node (ref "IC3") (pin "74") (pinfunction "(AD4)PA4_74") (pintype "bidirectional"))
      (node (ref "XIOH") (pin "12") (pinfunction "12_12") (pintype "passive"))
    )
    (net (code "33") (name "/PA5") (class "Default")
      (node (ref "IC3") (pin "73") (pinfunction "(AD5)PA5_73") (pintype "bidirectional"))
      (node (ref "XIOH") (pin "11") (pinfunction "11_11") (pintype "passive"))
    )
    (net (code "34") (name "/PA6") (class "Default")
      (node (ref "IC3") (pin "72") (pinfunction "(AD6)PA6_72") (pintype "bidirectional"))
      (node (ref "XIOH") (pin "10") (pinfunction "10_10") (pintype "passive"))
    )
    (net (code "35") (name "/PA7") (class "Default")
      (node (ref "IC3") (pin "71") (pinfunction "(AD7)PA7_71") (pintype "bidirectional"))
      (node (ref "XIOH") (pin "9") (pinfunction "9_9") (pintype "passive"))
    )
    (net (code "36") (name "/PB0") (class "Default")
      (node (ref "IC3") (pin "19") (pinfunction "(SS/PCINT0)PB0_19") (pintype "bidirectional"))
      (node (ref "XIOL") (pin "1") (pinfunction "1_1") (pintype "passive"))
    )
    (net (code "37") (name "/PB1") (class "Default")
      (node (ref "IC3") (pin "20") (pinfunction "(SCK/PCINT1)PB1_20") (pintype "bidirectional"))
      (node (ref "ICSP") (pin "3") (pinfunction "3_3") (pintype "passive"))
      (node (ref "XIOL") (pin "2") (pinfunction "2_2") (pintype "passive"))
    )
    (net (code "38") (name "/PB2") (class "Default")
      (node (ref "IC3") (pin "21") (pinfunction "(MOSI/PCINT2)PB2_21") (pintype "bidirectional"))
      (node (ref "ICSP") (pin "4") (pinfunction "4_4") (pintype "passive"))
      (node (ref "XIOL") (pin "3") (pinfunction "3_3") (pintype "passive"))
    )
    (net (code "39") (name "/PB3") (class "Default")
      (node (ref "IC3") (pin "22") (pinfunction "(MISO/PCINT3)PB3_22") (pintype "bidirectional"))
      (node (ref "ICSP") (pin "1") (pinfunction "1_1") (pintype "passive"))
      (node (ref "XIOL") (pin "4") (pinfunction "4_4") (pintype "passive"))
    )
    (net (code "40") (name "/PB4") (class "Default")
      (node (ref "IC3") (pin "23") (pinfunction "(OC2A/PCINT4)PB4_23") (pintype "bidirectional"))
      (node (ref "PWMH") (pin "3") (pinfunction "3_3") (pintype "passive"))
    )
    (net (code "41") (name "/PB5") (class "Default")
      (node (ref "IC3") (pin "24") (pinfunction "(OC1A/PCINT5)PB5_24") (pintype "bidirectional"))
      (node (ref "PWMH") (pin "4") (pinfunction "4_4") (pintype "passive"))
    )
    (net (code "42") (name "/PB6") (class "Default")
      (node (ref "IC3") (pin "25") (pinfunction "(OC1B/PCINT6)PB6_25") (pintype "bidirectional"))
      (node (ref "PWMH") (pin "5") (pinfunction "5_5") (pintype "passive"))
    )
    (net (code "43") (name "/PB7") (class "Default")
      (node (ref "IC3") (pin "26") (pinfunction "(OC0A/OC1C/PCINT7)PB7_26") (pintype "bidirectional"))
      (node (ref "PWMH") (pin "6") (pinfunction "6_6") (pintype "passive"))
      (node (ref "R7") (pin "2") (pinfunction "2_2") (pintype "passive"))
    )
    (net (code "44") (name "/PC0") (class "Default")
      (node (ref "IC3") (pin "53") (pinfunction "(A8)PC0_53") (pintype "bidirectional"))
      (node (ref "XIOH") (pin "1") (pinfunction "1_1") (pintype "passive"))
    )
    (net (code "45") (name "/PC1") (class "Default")
      (node (ref "IC3") (pin "54") (pinfunction "(A9)PC1_54") (pintype "bidirectional"))
      (node (ref "XIOH") (pin "2") (pinfunction "2_2") (pintype "passive"))
    )
    (net (code "46") (name "/PC2") (class "Default")
      (node (ref "IC3") (pin "55") (pinfunction "(A10)PC2_55") (pintype "bidirectional"))
      (node (ref "XIOH") (pin "3") (pinfunction "3_3") (pintype "passive"))
    )
    (net (code "47") (name "/PC3") (class "Default")
      (node (ref "IC3") (pin "56") (pinfunction "(A11)PC3_56") (pintype "bidirectional"))
      (node (ref "XIOH") (pin "4") (pinfunction "4_4") (pintype "passive"))
    )
    (net (code "48") (name "/PC4") (class "Default")
      (node (ref "IC3") (pin "57") (pinfunction "(A12)PC4_57") (pintype "bidirectional"))
      (node (ref "XIOH") (pin "5") (pinfunction "5_5") (pintype "passive"))
    )
    (net (code "49") (name "/PC5") (class "Default")
      (node (ref "IC3") (pin "58") (pinfunction "(A13)PC5_58") (pintype "bidirectional"))
      (node (ref "XIOH") (pin "6") (pinfunction "6_6") (pintype "passive"))
    )
    (net (code "50") (name "/PC6") (class "Default")
      (node (ref "IC3") (pin "59") (pinfunction "(A14)PC6_59") (pintype "bidirectional"))
      (node (ref "XIOH") (pin "7") (pinfunction "7_7") (pintype "passive"))
    )
    (net (code "51") (name "/PC7") (class "Default")
      (node (ref "IC3") (pin "60") (pinfunction "(A15)PC7_60") (pintype "bidirectional"))
      (node (ref "XIOH") (pin "8") (pinfunction "8_8") (pintype "passive"))
    )
    (net (code "52") (name "/PD7") (class "Default")
      (node (ref "IC3") (pin "50") (pinfunction "(T0)PD7_50") (pintype "bidirectional"))
      (node (ref "XIOL") (pin "16") (pinfunction "16_16") (pintype "passive"))
    )
    (net (code "53") (name "/PE0") (class "Default")
      (node (ref "IC3") (pin "2") (pinfunction "(RXD0/PCIN8)PE0_2") (pintype "bidirectional"))
      (node (ref "PWML") (pin "1") (pinfunction "1_1") (pintype "passive"))
      (node (ref "R16") (pin "2") (pinfunction "2_2") (pintype "passive"))
    )
    (net (code "54") (name "/PE1") (class "Default")
      (node (ref "IC3") (pin "3") (pinfunction "(TXD0)PE1_3") (pintype "bidirectional"))
      (node (ref "PWML") (pin "2") (pinfunction "2_2") (pintype "passive"))
      (node (ref "R15") (pin "2") (pinfunction "2_2") (pintype "passive"))
    )
    (net (code "55") (name "/PE3") (class "Default")
      (node (ref "IC3") (pin "5") (pinfunction "(OC3A/AIN1)PE3_5") (pintype "bidirectional"))
      (node (ref "PWML") (pin "6") (pinfunction "6_6") (pintype "passive"))
    )
    (net (code "56") (name "/PE4") (class "Default")
      (node (ref "IC3") (pin "6") (pinfunction "(OC3B/INT4)PE4_6") (pintype "bidirectional"))
      (node (ref "PWML") (pin "3") (pinfunction "3_3") (pintype "passive"))
    )
    (net (code "57") (name "/PE5") (class "Default")
      (node (ref "IC3") (pin "7") (pinfunction "(OC3C/INT5)PE5_7") (pintype "bidirectional"))
      (node (ref "PWML") (pin "4") (pinfunction "4_4") (pintype "passive"))
    )
    (net (code "58") (name "/PG0") (class "Default")
      (node (ref "IC3") (pin "51") (pinfunction "(WR)PG0_51") (pintype "bidirectional"))
      (node (ref "XIOL") (pin "13") (pinfunction "13_13") (pintype "passive"))
    )
    (net (code "59") (name "/PG1") (class "Default")
      (node (ref "IC3") (pin "52") (pinfunction "(RD)PG1_52") (pintype "bidirectional"))
      (node (ref "XIOL") (pin "14") (pinfunction "14_14") (pintype "passive"))
    )
    (net (code "60") (name "/PG2") (class "Default")
      (node (ref "IC3") (pin "70") (pinfunction "(ALE)PG2_70") (pintype "bidirectional"))
      (node (ref "XIOL") (pin "15") (pinfunction "15_15") (pintype "passive"))
    )
    (net (code "61") (name "/PG5") (class "Default")
      (node (ref "IC3") (pin "1") (pinfunction "(OC0B)PG5_1") (pintype "bidirectional"))
      (node (ref "PWML") (pin "5") (pinfunction "5_5") (pintype "passive"))
    )
    (net (code "62") (name "/PH3") (class "Default")
      (node (ref "IC3") (pin "15") (pinfunction "PH3(OC4A)_15") (pintype "bidirectional"))
      (node (ref "PWML") (pin "7") (pinfunction "7_7") (pintype "passive"))
    )
    (net (code "63") (name "/PH4") (class "Default")
      (node (ref "D1") (pin "A") (pinfunction "A_A") (pintype "passive"))
      (node (ref "IC3") (pin "16") (pinfunction "PH4(OC4B)_16") (pintype "bidirectional"))
      (node (ref "PWML") (pin "8") (pinfunction "8_8") (pintype "passive"))
    )
    (net (code "64") (name "/PH5") (class "Default")
      (node (ref "IC3") (pin "17") (pinfunction "PH5(OC4C)_17") (pintype "bidirectional"))
      (node (ref "PWMH") (pin "1") (pinfunction "1_1") (pintype "passive"))
    )
    (net (code "65") (name "/PH6") (class "Default")
      (node (ref "IC3") (pin "18") (pinfunction "PH6(OC2B)_18") (pintype "bidirectional"))
      (node (ref "PWMH") (pin "2") (pinfunction "2_2") (pintype "passive"))
    )
    (net (code "66") (name "/PL0") (class "Default")
      (node (ref "IC3") (pin "35") (pinfunction "PL0(ICP4)_35") (pintype "bidirectional"))
      (node (ref "XIOL") (pin "5") (pinfunction "5_5") (pintype "passive"))
    )
    (net (code "67") (name "/PL1") (class "Default")
      (node (ref "IC3") (pin "36") (pinfunction "PL1(ICP5)_36") (pintype "bidirectional"))
      (node (ref "XIOL") (pin "6") (pinfunction "6_6") (pintype "passive"))
    )
    (net (code "68") (name "/PL2") (class "Default")
      (node (ref "IC3") (pin "37") (pinfunction "PL2(T5)_37") (pintype "bidirectional"))
      (node (ref "XIOL") (pin "7") (pinfunction "7_7") (pintype "passive"))
    )
    (net (code "69") (name "/PL3") (class "Default")
      (node (ref "IC3") (pin "38") (pinfunction "PL3(OC5A)_38") (pintype "bidirectional"))
      (node (ref "XIOL") (pin "8") (pinfunction "8_8") (pintype "passive"))
    )
    (net (code "70") (name "/PL4") (class "Default")
      (node (ref "IC3") (pin "39") (pinfunction "PL4(OC5B)_39") (pintype "bidirectional"))
      (node (ref "XIOL") (pin "9") (pinfunction "9_9") (pintype "passive"))
    )
    (net (code "71") (name "/PL5") (class "Default")
      (node (ref "IC3") (pin "40") (pinfunction "PL5(OC5C)_40") (pintype "bidirectional"))
      (node (ref "XIOL") (pin "10") (pinfunction "10_10") (pintype "passive"))
    )
    (net (code "72") (name "/PL6") (class "Default")
      (node (ref "IC3") (pin "41") (pinfunction "PL6_41") (pintype "bidirectional"))
      (node (ref "XIOL") (pin "11") (pinfunction "11_11") (pintype "passive"))
    )
    (net (code "73") (name "/PL7") (class "Default")
      (node (ref "IC3") (pin "42") (pinfunction "PL7_42") (pintype "bidirectional"))
      (node (ref "XIOL") (pin "12") (pinfunction "12_12") (pintype "passive"))
    )
    (net (code "74") (name "/RESET") (class "Default")
      (node (ref "C1") (pin "1") (pinfunction "1_1") (pintype "passive"))
      (node (ref "C7") (pin "2") (pinfunction "2_2") (pintype "passive"))
      (node (ref "IC3") (pin "30") (pinfunction "RESET_30") (pintype "input"))
      (node (ref "ICSP") (pin "5") (pinfunction "5_5") (pintype "passive"))
      (node (ref "POWER") (pin "1") (pinfunction "1_1") (pintype "passive"))
      (node (ref "R6") (pin "2") (pinfunction "2_2") (pintype "passive"))
      (node (ref "RESET") (pin "3") (pinfunction "3_3") (pintype "passive"))
      (node (ref "RESET") (pin "4") (pinfunction "4_4") (pintype "passive"))
      (node (ref "RESET-EN") (pin "1") (pinfunction "1_1") (pintype "passive"))
      (node (ref "RESET-EN") (pin "2") (pinfunction "2_2") (pintype "passive"))
    )
    (net (code "75") (name "/RESET2") (class "Default")
      (node (ref "IC5") (pin "24") (pinfunction "RESET_24") (pintype "input"))
      (node (ref "ICSP1") (pin "5") (pinfunction "5_5") (pintype "passive"))
      (node (ref "R12") (pin "2") (pinfunction "2_2") (pintype "passive"))
    )
    (net (code "76") (name "/RXD1") (class "Default")
      (node (ref "COMMUNICATION") (pin "3") (pinfunction "3_3") (pintype "passive"))
      (node (ref "IC3") (pin "45") (pinfunction "(RXD1/INT2)PD2_45") (pintype "bidirectional"))
    )
    (net (code "77") (name "/RXD2") (class "Default")
      (node (ref "COMMUNICATION") (pin "5") (pinfunction "5_5") (pintype "passive"))
      (node (ref "IC3") (pin "12") (pinfunction "PH0(RXD2)_12") (pintype "bidirectional"))
      (node (ref "RELAY1") (pin "3") (pinfunction "+CONT_3") (pintype "bidirectional"))
    )
    (net (code "78") (name "/RXD3") (class "Default")
      (node (ref "COMMUNICATION") (pin "7") (pinfunction "7_7") (pintype "passive"))
      (node (ref "IC3") (pin "63") (pinfunction "PJ0(RXD3/PCINT9)_63") (pintype "bidirectional"))
    )
    (net (code "79") (name "/RXL") (class "Default")
      (node (ref "IC5") (pin "10") (pinfunction "PD4_10") (pintype "bidirectional"))
      (node (ref "LED4") (pin "C") (pinfunction "C_C") (pintype "passive"))
    )
    (net (code "80") (name "/SCK2") (class "Default")
      (node (ref "IC5") (pin "15") (pinfunction "PB1_15") (pintype "bidirectional"))
      (node (ref "ICSP1") (pin "3") (pinfunction "3_3") (pintype "passive"))
    )
    (net (code "81") (name "/SCL") (class "Default")
      (node (ref "COMMUNICATION") (pin "1") (pinfunction "1_1") (pintype "passive"))
      (node (ref "IC3") (pin "43") (pinfunction "(SCL/INT0)PD0_43") (pintype "bidirectional"))
      (node (ref "R9") (pin "2") (pinfunction "2_2") (pintype "passive"))
    )
    (net (code "82") (name "/SDA") (class "Default")
      (node (ref "COMMUNICATION") (pin "2") (pinfunction "2_2") (pintype "passive"))
      (node (ref "IC3") (pin "44") (pinfunction "(SDA/INT1)PD1_44") (pintype "bidirectional"))
      (node (ref "R8") (pin "2") (pinfunction "2_2") (pintype "passive"))
    )
    (net (code "83") (name "/TXD1") (class "Default")
      (node (ref "COMMUNICATION") (pin "4") (pinfunction "4_4") (pintype "passive"))
      (node (ref "IC3") (pin "46") (pinfunction "(TXD1/INT3)PD3_46") (pintype "bidirectional"))
    )
    (net (code "84") (name "/TXD2") (class "Default")
      (node (ref "COMMUNICATION") (pin "6") (pinfunction "6_6") (pintype "passive"))
      (node (ref "IC3") (pin "13") (pinfunction "PH1(TXD2)_13") (pintype "bidirectional"))
      (node (ref "RELAY2") (pin "3") (pinfunction "+CONT_3") (pintype "bidirectional"))
    )
    (net (code "85") (name "/TXD3") (class "Default")
      (node (ref "COMMUNICATION") (pin "8") (pinfunction "8_8") (pintype "passive"))
      (node (ref "IC3") (pin "64") (pinfunction "PJ1(TXD3/PCINT10)_64") (pintype "bidirectional"))
    )
    (net (code "86") (name "/TXL") (class "Default")
      (node (ref "IC5") (pin "11") (pinfunction "PD5_11") (pintype "bidirectional"))
      (node (ref "LED3") (pin "C") (pinfunction "C_C") (pintype "passive"))
    )
    (net (code "87") (name "/VUCAP") (class "Default")
      (node (ref "C10") (pin "1") (pinfunction "1_1") (pintype "passive"))
      (node (ref "IC5") (pin "27") (pinfunction "UCAP_27") (pintype "bidirectional"))
    )
    (net (code "88") (name "/XT1") (class "Default")
      (node (ref "R2") (pin "1") (pinfunction "1_1") (pintype "passive"))
      (node (ref "R4") (pin "2") (pinfunction "2_2") (pintype "passive"))
      (node (ref "Y2") (pin "3") (pinfunction "3_3") (pintype "bidirectional"))
    )
    (net (code "89") (name "/XT1R") (class "Default")
      (node (ref "IC5") (pin "1") (pinfunction "XTAL1_1") (pintype "bidirectional"))
      (node (ref "R4") (pin "1") (pinfunction "1_1") (pintype "passive"))
    )
    (net (code "90") (name "/XT2") (class "Default")
      (node (ref "IC5") (pin "2") (pinfunction "XTAL2_2") (pintype "bidirectional"))
      (node (ref "R2") (pin "2") (pinfunction "2_2") (pintype "passive"))
      (node (ref "Y2") (pin "1") (pinfunction "1_1") (pintype "bidirectional"))
    )
    (net (code "91") (name "/XTAL1") (class "Default")
      (node (ref "R1") (pin "1") (pinfunction "1_1") (pintype "passive"))
      (node (ref "R3") (pin "2") (pinfunction "2_2") (pintype "passive"))
      (node (ref "Y1") (pin "3") (pinfunction "3_3") (pintype "bidirectional"))
    )
    (net (code "92") (name "/XTAL1R") (class "Default")
      (node (ref "IC3") (pin "34") (pinfunction "XTAL1_34") (pintype "input"))
      (node (ref "R3") (pin "1") (pinfunction "1_1") (pintype "passive"))
    )
    (net (code "93") (name "/XTAL2") (class "Default")
      (node (ref "IC3") (pin "33") (pinfunction "XTAL2_33") (pintype "output"))
      (node (ref "R1") (pin "2") (pinfunction "2_2") (pintype "passive"))
      (node (ref "Y1") (pin "1") (pinfunction "1_1") (pintype "bidirectional"))
    )
    (net (code "94") (name "GND") (class "Default")
      (node (ref "C1") (pin "2") (pinfunction "2_2") (pintype "passive"))
      (node (ref "C10") (pin "2") (pinfunction "2_2") (pintype "passive"))
      (node (ref "C11") (pin "1") (pinfunction "1_1") (pintype "passive"))
      (node (ref "C12") (pin "1") (pinfunction "1_1") (pintype "passive"))
      (node (ref "C13") (pin "1") (pinfunction "1_1") (pintype "passive"))
      (node (ref "C14") (pin "1") (pinfunction "1_1") (pintype "passive"))
      (node (ref "C15") (pin "1") (pinfunction "1_1") (pintype "passive"))
      (node (ref "C16") (pin "1") (pinfunction "1_1") (pintype "passive"))
      (node (ref "C17") (pin "1") (pinfunction "1_1") (pintype "passive"))
      (node (ref "C18") (pin "1") (pinfunction "1_1") (pintype "passive"))
      (node (ref "C19") (pin "1") (pinfunction "1_1") (pintype "passive"))
      (node (ref "C2") (pin "2") (pinfunction "2_2") (pintype "passive"))
      (node (ref "C20") (pin "2") (pinfunction "2_2") (pintype "passive"))
      (node (ref "C21") (pin "2") (pinfunction "2_2") (pintype "passive"))
      (node (ref "C22") (pin "2") (pinfunction "2_2") (pintype "passive"))
      (node (ref "C24") (pin "2") (pinfunction "2_2") (pintype "passive"))
      (node (ref "C25") (pin "2") (pinfunction "2_2") (pintype "passive"))
      (node (ref "C26") (pin "2") (pinfunction "2_2") (pintype "passive"))
      (node (ref "C27") (pin "2") (pinfunction "2_2") (pintype "passive"))
      (node (ref "C3") (pin "2") (pinfunction "2_2") (pintype "passive"))
      (node (ref "C4") (pin "2") (pinfunction "2_2") (pintype "passive"))
      (node (ref "C5") (pin "2") (pinfunction "2_2") (pintype "passive"))
      (node (ref "C6") (pin "2") (pinfunction "2_2") (pintype "passive"))
      (node (ref "C8") (pin "2") (pinfunction "2_2") (pintype "passive"))
      (node (ref "C9") (pin "2") (pinfunction "2_2") (pintype "passive"))
      (node (ref "D3") (pin "1") (pinfunction "A_1") (pintype "passive"))
      (node (ref "IC1") (pin "1") (pinfunction "GND/ADJ_1") (pintype "input"))
      (node (ref "IC2") (pin "1") (pinfunction "ADJ_1") (pintype "input"))
      (node (ref "IC3") (pin "11") (pinfunction "GND_11") (pintype "power_in"))
      (node (ref "IC3") (pin "32") (pinfunction "GND1_32") (pintype "power_in"))
      (node (ref "IC3") (pin "62") (pinfunction "GND2_62") (pintype "power_in"))
      (node (ref "IC3") (pin "81") (pinfunction "GND3_81") (pintype "power_in"))
      (node (ref "IC3") (pin "99") (pinfunction "AGND_99") (pintype "power_in"))
      (node (ref "IC4") (pin "28") (pinfunction "GND_28") (pintype "power_in"))
      (node (ref "IC4") (pin "6") (pinfunction "EEDAT/GANG_6") (pintype "bidirectional"))
      (node (ref "IC4") (pin "7") (pinfunction "GND_7") (pintype "power_in"))
      (node (ref "IC4") (pin "8") (pinfunction "BUSPWR_8") (pintype "input"))
      (node (ref "IC5") (pin "28") (pinfunction "UGND_28") (pintype "power_in"))
      (node (ref "IC5") (pin "3") (pinfunction "GND_3") (pintype "bidirectional"))
      (node (ref "IC6") (pin "2") (pinfunction "GND_2") (pintype "power_in"))
      (node (ref "IC8") (pin "1") (pinfunction "GND_1") (pintype "bidirectional"))
      (node (ref "IC8") (pin "GG") (pinfunction "GG_GG") (pintype "bidirectional"))
      (node (ref "IC9") (pin "5") (pinfunction "GND_5") (pintype "bidirectional"))
      (node (ref "ICSP") (pin "6") (pinfunction "6_6") (pintype "passive"))
      (node (ref "ICSP1") (pin "6") (pinfunction "6_6") (pintype "passive"))
      (node (ref "J43") (pin "4") (pinfunction "-_4") (pintype "bidirectional"))
      (node (ref "J43") (pin "G1") (pinfunction "G1_G1") (pintype "bidirectional"))
      (node (ref "J43") (pin "G2") (pinfunction "G2_G2") (pintype "bidirectional"))
      (node (ref "J44") (pin "-") (pinfunction "-_-") (pintype "bidirectional"))
      (node (ref "J44") (pin "G1") (pinfunction "G1_G1") (pintype "bidirectional"))
      (node (ref "J44") (pin "G2") (pinfunction "G2_G2") (pintype "bidirectional"))
      (node (ref "J45") (pin "-") (pinfunction "-_-") (pintype "bidirectional"))
      (node (ref "J45") (pin "G1") (pinfunction "G1_G1") (pintype "bidirectional"))
      (node (ref "J45") (pin "G2") (pinfunction "G2_G2") (pintype "bidirectional"))
      (node (ref "J49") (pin "2") (pinfunction "2_2") (pintype "bidirectional"))
      (node (ref "JP3") (pin "1") (pinfunction "1_1") (pintype "passive"))
      (node (ref "JP4") (pin "1") (pinfunction "1_1") (pintype "passive"))
      (node (ref "LED2") (pin "C") (pinfunction "C_C") (pintype "passive"))
      (node (ref "ON") (pin "C") (pinfunction "C_C") (pintype "passive"))
      (node (ref "PC1") (pin "-") (pinfunction "-_-") (pintype "passive"))
      (node (ref "PC10") (pin "-") (pinfunction "-_-") (pintype "passive"))
      (node (ref "PC11") (pin "-") (pinfunction "-_-") (pintype "passive"))
      (node (ref "PC12") (pin "-") (pinfunction "-_-") (pintype "passive"))
      (node (ref "PC2") (pin "-") (pinfunction "-_-") (pintype "passive"))
      (node (ref "PC3") (pin "-") (pinfunction "-_-") (pintype "passive"))
      (node (ref "PC6") (pin "-") (pinfunction "-_-") (pintype "passive"))
      (node (ref "PC7") (pin "-") (pinfunction "-_-") (pintype "passive"))
      (node (ref "PC8") (pin "-") (pinfunction "-_-") (pintype "passive"))
      (node (ref "PC9") (pin "-") (pinfunction "-_-") (pintype "passive"))
      (node (ref "POWER") (pin "4") (pinfunction "4_4") (pintype "passive"))
      (node (ref "POWER") (pin "5") (pinfunction "5_5") (pintype "passive"))
      (node (ref "PWMH") (pin "7") (pinfunction "7_7") (pintype "passive"))
      (node (ref "Q2") (pin "E") (pinfunction "E_E") (pintype "passive"))
      (node (ref "R30") (pin "2") (pinfunction "2_2") (pintype "passive"))
      (node (ref "R31") (pin "2") (pinfunction "2_2") (pintype "passive"))
      (node (ref "R32") (pin "2") (pinfunction "2_2") (pintype "passive"))
      (node (ref "R33") (pin "2") (pinfunction "2_2") (pintype "passive"))
      (node (ref "R34") (pin "2") (pinfunction "2_2") (pintype "passive"))
      (node (ref "R35") (pin "2") (pinfunction "2_2") (pintype "passive"))
      (node (ref "R36") (pin "2") (pinfunction "2_2") (pintype "passive"))
      (node (ref "R37") (pin "2") (pinfunction "2_2") (pintype "passive"))
      (node (ref "R40") (pin "2") (pinfunction "2_2") (pintype "passive"))
      (node (ref "R41") (pin "2") (pinfunction "2_2") (pintype "passive"))
      (node (ref "R42") (pin "2") (pinfunction "2_2") (pintype "passive"))
      (node (ref "R44") (pin "2") (pinfunction "2_2") (pintype "passive"))
      (node (ref "R48") (pin "2") (pinfunction "2_2") (pintype "passive"))
      (node (ref "RELAY1") (pin "4") (pinfunction "-CONT_4") (pintype "bidirectional"))
      (node (ref "RELAY2") (pin "4") (pinfunction "-CONT_4") (pintype "bidirectional"))
      (node (ref "RESET") (pin "1") (pinfunction "1_1") (pintype "passive"))
      (node (ref "RESET") (pin "2") (pinfunction "2_2") (pintype "passive"))
      (node (ref "SV1") (pin "4") (pinfunction "4_4") (pintype "passive"))
      (node (ref "U$1") (pin "4") (pinfunction "GND_4") (pintype "bidirectional"))
      (node (ref "UBOOT") (pin "2") (pinfunction "2_2") (pintype "passive"))
      (node (ref "Y1") (pin "2") (pinfunction "2_2") (pintype "bidirectional"))
      (node (ref "Y2") (pin "2") (pinfunction "2_2") (pintype "bidirectional"))
      (node (ref "Y3") (pin "2") (pinfunction "GND_2") (pintype "bidirectional"))
    )
    (net (code "95") (name "Net-(D1-PadC)") (class "Default")
      (node (ref "D1") (pin "C") (pinfunction "C_C") (pintype "passive"))
      (node (ref "R24") (pin "2") (pinfunction "2_2") (pintype "passive"))
    )
    (net (code "96") (name "Net-(D2-C)") (class "Default")
      (node (ref "C23") (pin "2") (pinfunction "2_2") (pintype "passive"))
      (node (ref "D2") (pin "K") (pinfunction "C_K") (pintype "passive"))
      (node (ref "J47") (pin "4") (pinfunction "4_4") (pintype "bidirectional"))
      (node (ref "PC4") (pin "+") (pinfunction "+_+") (pintype "passive"))
      (node (ref "PC5") (pin "+") (pinfunction "+_+") (pintype "passive"))
    )
    (net (code "97") (name "Net-(D3-C)") (class "Default")
      (node (ref "C22") (pin "1") (pinfunction "1_1") (pintype "passive"))
      (node (ref "D3") (pin "3") (pinfunction "C_3") (pintype "passive"))
      (node (ref "IC9") (pin "8") (pinfunction "IN_8") (pintype "bidirectional"))
      (node (ref "R45") (pin "2") (pinfunction "2_2") (pintype "passive"))
    )
    (net (code "98") (name "Net-(D5-C)") (class "Default")
      (node (ref "D4") (pin "A") (pinfunction "A_A") (pintype "passive"))
      (node (ref "D5") (pin "K") (pinfunction "C_K") (pintype "passive"))
      (node (ref "IC7") (pin "2") (pinfunction "OUT_2") (pintype "passive"))
      (node (ref "J47") (pin "2") (pinfunction "2_2") (pintype "bidirectional"))
      (node (ref "PC11") (pin "+") (pinfunction "+_+") (pintype "passive"))
      (node (ref "R47") (pin "1") (pinfunction "1_1") (pintype "passive"))
    )
    (net (code "99") (name "Net-(F2-Pad1)") (class "Default")
      (node (ref "F2") (pin "1") (pinfunction "1_1") (pintype "bidirectional"))
      (node (ref "F3") (pin "1") (pinfunction "1_1") (pintype "bidirectional"))
      (node (ref "J49") (pin "1") (pinfunction "1_1") (pintype "bidirectional"))
    )
    (net (code "100") (name "Net-(IC2-VO)") (class "Default")
      (node (ref "F1") (pin "1") (pinfunction "1_1") (pintype "bidirectional"))
      (node (ref "IC1") (pin "2") (pinfunction "OUT_2") (pintype "passive"))
      (node (ref "IC1") (pin "4") (pinfunction "OUT_4") (pintype "passive"))
      (node (ref "IC2") (pin "2") (pinfunction "VO_2") (pintype "passive"))
    )
    (net (code "101") (name "Net-(IC4-DM0)") (class "Default")
      (node (ref "C20") (pin "1") (pinfunction "1_1") (pintype "passive"))
      (node (ref "IC4") (pin "2") (pinfunction "DM0_2") (pintype "bidirectional"))
      (node (ref "R19") (pin "1") (pinfunction "1_1") (pintype "passive"))
    )
    (net (code "102") (name "Net-(IC4-DM1)") (class "Default")
      (node (ref "C19") (pin "2") (pinfunction "2_2") (pintype "passive"))
      (node (ref "IC4") (pin "11") (pinfunction "DM1_11") (pintype "bidirectional"))
      (node (ref "R22") (pin "2") (pinfunction "2_2") (pintype "passive"))
    )
    (net (code "103") (name "Net-(IC4-DM2)") (class "Default")
      (node (ref "C16") (pin "2") (pinfunction "2_2") (pintype "passive"))
      (node (ref "IC4") (pin "15") (pinfunction "DM2_15") (pintype "bidirectional"))
      (node (ref "R29") (pin "2") (pinfunction "2_2") (pintype "passive"))
    )
    (net (code "104") (name "Net-(IC4-DM3)") (class "Default")
      (node (ref "C12") (pin "2") (pinfunction "2_2") (pintype "passive"))
      (node (ref "IC4") (pin "19") (pinfunction "DM3_19") (pintype "bidirectional"))
      (node (ref "R25") (pin "2") (pinfunction "2_2") (pintype "passive"))
    )
    (net (code "105") (name "Net-(IC4-DM4)") (class "Default")
      (node (ref "C11") (pin "2") (pinfunction "2_2") (pintype "passive"))
      (node (ref "IC4") (pin "23") (pinfunction "DM4_23") (pintype "bidirectional"))
      (node (ref "R27") (pin "2") (pinfunction "2_2") (pintype "passive"))
    )
    (net (code "106") (name "Net-(IC4-DP0)") (class "Default")
      (node (ref "C21") (pin "1") (pinfunction "1_1") (pintype "passive"))
      (node (ref "IC4") (pin "1") (pinfunction "DP0_1") (pintype "bidirectional"))
      (node (ref "R17") (pin "1") (pinfunction "1_1") (pintype "passive"))
      (node (ref "R18") (pin "1") (pinfunction "1_1") (pintype "passive"))
    )
    (net (code "107") (name "Net-(IC4-DP1)") (class "Default")
      (node (ref "C18") (pin "2") (pinfunction "2_2") (pintype "passive"))
      (node (ref "IC4") (pin "12") (pinfunction "DP1_12") (pintype "bidirectional"))
      (node (ref "R21") (pin "2") (pinfunction "2_2") (pintype "passive"))
    )
    (net (code "108") (name "Net-(IC4-DP2)") (class "Default")
      (node (ref "C17") (pin "2") (pinfunction "2_2") (pintype "passive"))
      (node (ref "IC4") (pin "16") (pinfunction "DP2_16") (pintype "bidirectional"))
      (node (ref "R28") (pin "2") (pinfunction "2_2") (pintype "passive"))
    )
    (net (code "109") (name "Net-(IC4-DP3)") (class "Default")
      (node (ref "C15") (pin "2") (pinfunction "2_2") (pintype "passive"))
      (node (ref "IC4") (pin "20") (pinfunction "DP3_20") (pintype "bidirectional"))
      (node (ref "R23") (pin "2") (pinfunction "2_2") (pintype "passive"))
    )
    (net (code "110") (name "Net-(IC4-DP4)") (class "Default")
      (node (ref "C14") (pin "2") (pinfunction "2_2") (pintype "passive"))
      (node (ref "IC4") (pin "24") (pinfunction "DP4_24") (pintype "bidirectional"))
      (node (ref "R26") (pin "2") (pinfunction "2_2") (pintype "passive"))
    )
    (net (code "111") (name "Net-(IC4-TST{slash}48M)") (class "Default")
      (node (ref "IC4") (pin "27") (pinfunction "TST/48M_27") (pintype "bidirectional"))
      (node (ref "Y3") (pin "3") (pinfunction "OUT_3") (pintype "bidirectional"))
    )
    (net (code "112") (name "Net-(IC4-~{OVR1})") (class "Default")
      (node (ref "IC4") (pin "10") (pinfunction "~{OVR1}_10") (pintype "input"))
      (node (ref "R10") (pin "1") (pinfunction "1_1") (pintype "passive"))
    )
    (net (code "113") (name "Net-(IC4-~{OVR2})") (class "Default")
      (node (ref "IC4") (pin "14") (pinfunction "~{OVR2}_14") (pintype "input"))
      (node (ref "R11") (pin "1") (pinfunction "1_1") (pintype "passive"))
    )
    (net (code "114") (name "Net-(IC4-~{OVR3})") (class "Default")
      (node (ref "IC4") (pin "18") (pinfunction "~{OVR3}_18") (pintype "input"))
      (node (ref "IC8") (pin "5") (pinfunction "OC2_5") (pintype "bidirectional"))
      (node (ref "R50") (pin "1") (pinfunction "1_1") (pintype "passive"))
    )
    (net (code "115") (name "Net-(IC4-~{OVR4})") (class "Default")
      (node (ref "IC4") (pin "22") (pinfunction "~{OVR4}_22") (pintype "input"))
      (node (ref "IC8") (pin "8") (pinfunction "OC1_8") (pintype "bidirectional"))
      (node (ref "R51") (pin "1") (pinfunction "1_1") (pintype "passive"))
    )
    (net (code "116") (name "Net-(IC4-~{PWR3})") (class "Default")
      (node (ref "IC4") (pin "17") (pinfunction "~{PWR3}_17") (pintype "output"))
      (node (ref "IC8") (pin "4") (pinfunction "ENE_4") (pintype "bidirectional"))
    )
    (net (code "117") (name "Net-(IC4-~{PWR4})") (class "Default")
      (node (ref "IC4") (pin "21") (pinfunction "~{PWR4}_21") (pintype "output"))
      (node (ref "IC8") (pin "3") (pinfunction "EN1_3") (pintype "bidirectional"))
    )
    (net (code "118") (name "Net-(IC4-~{RESET})") (class "Default")
      (node (ref "C8") (pin "1") (pinfunction "1_1") (pintype "passive"))
      (node (ref "IC4") (pin "4") (pinfunction "~{RESET}_4") (pintype "input"))
      (node (ref "R20") (pin "1") (pinfunction "1_1") (pintype "passive"))
    )
    (net (code "119") (name "Net-(IC5-D+)") (class "Default")
      (node (ref "IC5") (pin "29") (pinfunction "D+_29") (pintype "bidirectional"))
      (node (ref "R21") (pin "1") (pinfunction "1_1") (pintype "passive"))
      (node (ref "R30") (pin "1") (pinfunction "1_1") (pintype "passive"))
    )
    (net (code "120") (name "Net-(IC5-D-)") (class "Default")
      (node (ref "IC5") (pin "30") (pinfunction "D-_30") (pintype "bidirectional"))
      (node (ref "R22") (pin "1") (pinfunction "1_1") (pintype "passive"))
      (node (ref "R31") (pin "1") (pinfunction "1_1") (pintype "passive"))
    )
    (net (code "121") (name "Net-(IC7-ADJ)") (class "Default")
      (node (ref "D5") (pin "A") (pinfunction "A_A") (pintype "passive"))
      (node (ref "IC7") (pin "1") (pinfunction "ADJ_1") (pintype "input"))
      (node (ref "PC10") (pin "+") (pinfunction "+_+") (pintype "passive"))
      (node (ref "R47") (pin "2") (pinfunction "2_2") (pintype "passive"))
      (node (ref "R48") (pin "1") (pinfunction "1_1") (pintype "passive"))
    )
    (net (code "122") (name "Net-(IC8-OUT1)") (class "Default")
      (node (ref "IC8") (pin "7") (pinfunction "OUT1_7") (pintype "bidirectional"))
      (node (ref "J45") (pin "+") (pinfunction "+_+") (pintype "bidirectional"))
      (node (ref "PC8") (pin "+") (pinfunction "+_+") (pintype "passive"))
    )
    (net (code "123") (name "Net-(IC8-OUT2)") (class "Default")
      (node (ref "IC8") (pin "6") (pinfunction "OUT2_6") (pintype "bidirectional"))
      (node (ref "J44") (pin "+") (pinfunction "+_+") (pintype "bidirectional"))
      (node (ref "PC3") (pin "+") (pinfunction "+_+") (pintype "passive"))
    )
    (net (code "124") (name "Net-(IC9-CS)") (class "Default")
      (node (ref "C25") (pin "1") (pinfunction "1_1") (pintype "passive"))
      (node (ref "IC9") (pin "4") (pinfunction "CS_4") (pintype "bidirectional"))
      (node (ref "R42") (pin "1") (pinfunction "1_1") (pintype "passive"))
      (node (ref "R43") (pin "2") (pinfunction "2_2") (pintype "passive"))
    )
    (net (code "125") (name "Net-(IC9-DIM{slash}FB)") (class "Default")
      (node (ref "C26") (pin "1") (pinfunction "1_1") (pintype "passive"))
      (node (ref "IC9") (pin "2") (pinfunction "DIM/FB_2") (pintype "bidirectional"))
      (node (ref "R24") (pin "1") (pinfunction "1_1") (pintype "passive"))
      (node (ref "R39") (pin "2") (pinfunction "2_2") (pintype "passive"))
      (node (ref "R40") (pin "1") (pinfunction "1_1") (pintype "passive"))
    )
    (net (code "126") (name "Net-(IC9-NDRV)") (class "Default")
      (node (ref "IC9") (pin "6") (pinfunction "NDRV_6") (pintype "bidirectional"))
      (node (ref "R46") (pin "2") (pinfunction "2_2") (pintype "passive"))
    )
    (net (code "127") (name "Net-(IC9-UVLO{slash}EN)") (class "Default")
      (node (ref "IC9") (pin "1") (pinfunction "UVLO/EN_1") (pintype "bidirectional"))
      (node (ref "R38") (pin "2") (pinfunction "2_2") (pintype "passive"))
      (node (ref "R41") (pin "1") (pinfunction "1_1") (pintype "passive"))
    )
    (net (code "128") (name "Net-(IC9-VCC)") (class "Default")
      (node (ref "C24") (pin "1") (pinfunction "1_1") (pintype "passive"))
      (node (ref "IC9") (pin "7") (pinfunction "VCC_7") (pintype "bidirectional"))
    )
    (net (code "129") (name "Net-(J43-D+)") (class "Default")
      (node (ref "J43") (pin "3") (pinfunction "D+_3") (pintype "bidirectional"))
      (node (ref "R18") (pin "2") (pinfunction "2_2") (pintype "passive"))
    )
    (net (code "130") (name "Net-(J43-D-)") (class "Default")
      (node (ref "J43") (pin "2") (pinfunction "D-_2") (pintype "bidirectional"))
      (node (ref "R19") (pin "2") (pinfunction "2_2") (pintype "passive"))
    )
    (net (code "131") (name "Net-(J44-PadD+)") (class "Default")
      (node (ref "J44") (pin "D+") (pinfunction "D+_D+") (pintype "bidirectional"))
      (node (ref "R23") (pin "1") (pinfunction "1_1") (pintype "passive"))
      (node (ref "R37") (pin "1") (pinfunction "1_1") (pintype "passive"))
    )
    (net (code "132") (name "Net-(J44-PadD-)") (class "Default")
      (node (ref "J44") (pin "D-") (pinfunction "D-_D-") (pintype "bidirectional"))
      (node (ref "R25") (pin "1") (pinfunction "1_1") (pintype "passive"))
      (node (ref "R36") (pin "1") (pinfunction "1_1") (pintype "passive"))
    )
    (net (code "133") (name "Net-(J45-PadD+)") (class "Default")
      (node (ref "J45") (pin "D+") (pinfunction "D+_D+") (pintype "bidirectional"))
      (node (ref "R26") (pin "1") (pinfunction "1_1") (pintype "passive"))
      (node (ref "R35") (pin "1") (pinfunction "1_1") (pintype "passive"))
    )
    (net (code "134") (name "Net-(J45-PadD-)") (class "Default")
      (node (ref "J45") (pin "D-") (pinfunction "D-_D-") (pintype "bidirectional"))
      (node (ref "R27") (pin "1") (pinfunction "1_1") (pintype "passive"))
      (node (ref "R34") (pin "1") (pinfunction "1_1") (pintype "passive"))
    )
    (net (code "135") (name "Net-(J47-Pad1)") (class "Default")
      (node (ref "J47") (pin "1") (pinfunction "1_1") (pintype "bidirectional"))
      (node (ref "Q2") (pin "C") (pinfunction "C_C") (pintype "passive"))
    )
    (net (code "136") (name "Net-(LED2-PadA)") (class "Default")
      (node (ref "LED2") (pin "A") (pinfunction "A_A") (pintype "passive"))
      (node (ref "R7") (pin "1") (pinfunction "1_1") (pintype "passive"))
    )
    (net (code "137") (name "Net-(LED3-PadA)") (class "Default")
      (node (ref "LED3") (pin "A") (pinfunction "A_A") (pintype "passive"))
      (node (ref "R13") (pin "2") (pinfunction "2_2") (pintype "passive"))
    )
    (net (code "138") (name "Net-(LED4-PadA)") (class "Default")
      (node (ref "LED4") (pin "A") (pinfunction "A_A") (pintype "passive"))
      (node (ref "R14") (pin "2") (pinfunction "2_2") (pintype "passive"))
    )
    (net (code "139") (name "Net-(ON-PadA)") (class "Default")
      (node (ref "ON") (pin "A") (pinfunction "A_A") (pintype "passive"))
      (node (ref "R5") (pin "1") (pinfunction "1_1") (pintype "passive"))
    )
    (net (code "140") (name "Net-(Q2-PadB)") (class "Default")
      (node (ref "Q2") (pin "B") (pinfunction "B_B") (pintype "passive"))
      (node (ref "R49") (pin "2") (pinfunction "2_2") (pintype "passive"))
    )
    (net (code "141") (name "Net-(R28-Pad1)") (class "Default")
      (node (ref "R28") (pin "1") (pinfunction "1_1") (pintype "passive"))
      (node (ref "R33") (pin "1") (pinfunction "1_1") (pintype "passive"))
      (node (ref "SV1") (pin "2") (pinfunction "2_2") (pintype "passive"))
    )
    (net (code "142") (name "Net-(R29-Pad1)") (class "Default")
      (node (ref "R29") (pin "1") (pinfunction "1_1") (pintype "passive"))
      (node (ref "R32") (pin "1") (pinfunction "1_1") (pintype "passive"))
      (node (ref "SV1") (pin "3") (pinfunction "3_3") (pintype "passive"))
    )
    (net (code "143") (name "Net-(RELAY1-+LOAD)") (class "Default")
      (node (ref "J46") (pin "3") (pinfunction "3_3") (pintype "bidirectional"))
      (node (ref "RELAY1") (pin "1") (pinfunction "+LOAD_1") (pintype "bidirectional"))
    )
    (net (code "144") (name "Net-(RELAY1--LOAD)") (class "Default")
      (node (ref "J46") (pin "4") (pinfunction "4_4") (pintype "bidirectional"))
      (node (ref "RELAY1") (pin "2") (pinfunction "-LOAD_2") (pintype "bidirectional"))
    )
    (net (code "145") (name "Net-(RELAY2-+LOAD)") (class "Default")
      (node (ref "J46") (pin "1") (pinfunction "1_1") (pintype "bidirectional"))
      (node (ref "RELAY2") (pin "1") (pinfunction "+LOAD_1") (pintype "bidirectional"))
    )
    (net (code "146") (name "Net-(RELAY2--LOAD)") (class "Default")
      (node (ref "J46") (pin "2") (pinfunction "2_2") (pintype "bidirectional"))
      (node (ref "RELAY2") (pin "2") (pinfunction "-LOAD_2") (pintype "bidirectional"))
    )
    (net (code "147") (name "Net-(U$6-D1)") (class "Default")
      (node (ref "D2") (pin "A") (pinfunction "A_A") (pintype "passive"))
      (node (ref "L1") (pin "1") (pinfunction "1_1") (pintype "bidirectional"))
      (node (ref "R39") (pin "1") (pinfunction "1_1") (pintype "passive"))
      (node (ref "U$6") (pin "1") (pinfunction "D1_1") (pintype "bidirectional"))
      (node (ref "U$6") (pin "2") (pinfunction "D2_2") (pintype "bidirectional"))
      (node (ref "U$6") (pin "5") (pinfunction "D3_5") (pintype "bidirectional"))
      (node (ref "U$6") (pin "6") (pinfunction "D4_6") (pintype "bidirectional"))
    )
    (net (code "148") (name "Net-(U$6-G)") (class "Default")
      (node (ref "R46") (pin "1") (pinfunction "1_1") (pintype "passive"))
      (node (ref "U$6") (pin "3") (pinfunction "G_3") (pintype "bidirectional"))
    )
    (net (code "149") (name "Net-(U$6-S)") (class "Default")
      (node (ref "R43") (pin "1") (pinfunction "1_1") (pintype "passive"))
      (node (ref "R44") (pin "1") (pinfunction "1_1") (pintype "passive"))
      (node (ref "U$6") (pin "4") (pinfunction "S_4") (pintype "bidirectional"))
    )
    (net (code "150") (name "unconnected-(IC3-(CLKO{slash}ICP3{slash}INT7)PE7-Pad9)") (class "Default")
      (node (ref "IC3") (pin "9") (pinfunction "(CLKO/ICP3/INT7)PE7_9") (pintype "bidirectional"))
    )
    (net (code "151") (name "unconnected-(IC3-(ICP1)PD4-Pad47)") (class "Default")
      (node (ref "IC3") (pin "47") (pinfunction "(ICP1)PD4_47") (pintype "bidirectional"))
    )
    (net (code "152") (name "unconnected-(IC3-(T1)PD6-Pad49)") (class "Default")
      (node (ref "IC3") (pin "49") (pinfunction "(T1)PD6_49") (pintype "bidirectional"))
    )
    (net (code "153") (name "unconnected-(IC3-(T3{slash}INT6)PE6-Pad8)") (class "Default")
      (node (ref "IC3") (pin "8") (pinfunction "(T3/INT6)PE6_8") (pintype "bidirectional"))
    )
    (net (code "154") (name "unconnected-(IC3-(TOSC1)PG4-Pad29)") (class "Default")
      (node (ref "IC3") (pin "29") (pinfunction "(TOSC1)PG4_29") (pintype "bidirectional"))
    )
    (net (code "155") (name "unconnected-(IC3-(TOSC2)PG3-Pad28)") (class "Default")
      (node (ref "IC3") (pin "28") (pinfunction "(TOSC2)PG3_28") (pintype "bidirectional"))
    )
    (net (code "156") (name "unconnected-(IC3-(XCK0{slash}AIN0)PE2-Pad4)") (class "Default")
      (node (ref "IC3") (pin "4") (pinfunction "(XCK0/AIN0)PE2_4") (pintype "bidirectional"))
    )
    (net (code "157") (name "unconnected-(IC3-(XCK1)PD5-Pad48)") (class "Default")
      (node (ref "IC3") (pin "48") (pinfunction "(XCK1)PD5_48") (pintype "bidirectional"))
    )
    (net (code "158") (name "unconnected-(IC3-PH2(XCK2)-Pad14)") (class "Default")
      (node (ref "IC3") (pin "14") (pinfunction "PH2(XCK2)_14") (pintype "bidirectional"))
    )
    (net (code "159") (name "unconnected-(IC3-PH7(T4)-Pad27)") (class "Default")
      (node (ref "IC3") (pin "27") (pinfunction "PH7(T4)_27") (pintype "bidirectional"))
    )
    (net (code "160") (name "unconnected-(IC3-PJ2(XCK3{slash}PCINT11)-Pad65)") (class "Default")
      (node (ref "IC3") (pin "65") (pinfunction "PJ2(XCK3/PCINT11)_65") (pintype "bidirectional"))
    )
    (net (code "161") (name "unconnected-(IC3-PJ3(PCINT12)-Pad66)") (class "Default")
      (node (ref "IC3") (pin "66") (pinfunction "PJ3(PCINT12)_66") (pintype "bidirectional"))
    )
    (net (code "162") (name "unconnected-(IC3-PJ4(PCINT13)-Pad67)") (class "Default")
      (node (ref "IC3") (pin "67") (pinfunction "PJ4(PCINT13)_67") (pintype "bidirectional"))
    )
    (net (code "163") (name "unconnected-(IC3-PJ5(PCINT14)-Pad68)") (class "Default")
      (node (ref "IC3") (pin "68") (pinfunction "PJ5(PCINT14)_68") (pintype "bidirectional"))
    )
    (net (code "164") (name "unconnected-(IC3-PJ6(PCINT15)-Pad69)") (class "Default")
      (node (ref "IC3") (pin "69") (pinfunction "PJ6(PCINT15)_69") (pintype "bidirectional"))
    )
    (net (code "165") (name "unconnected-(IC3-PJ7-Pad79)") (class "Default")
      (node (ref "IC3") (pin "79") (pinfunction "PJ7_79") (pintype "bidirectional"))
    )
    (net (code "166") (name "unconnected-(IC4-EECLK-Pad5)") (class "Default")
      (node (ref "IC4") (pin "5") (pinfunction "EECLK_5") (pintype "bidirectional"))
    )
    (net (code "167") (name "unconnected-(IC4-SUSPEND-Pad32)") (class "Default")
      (node (ref "IC4") (pin "32") (pinfunction "SUSPEND_32") (pintype "output"))
    )
    (net (code "168") (name "unconnected-(IC4-XTAL2-Pad29)") (class "Default")
      (node (ref "IC4") (pin "29") (pinfunction "XTAL2_29") (pintype "bidirectional"))
    )
    (net (code "169") (name "unconnected-(IC4-~{PWR1}-Pad9)") (class "Default")
      (node (ref "IC4") (pin "9") (pinfunction "~{PWR1}_9") (pintype "output"))
    )
    (net (code "170") (name "unconnected-(IC4-~{PWR2}-Pad13)") (class "Default")
      (node (ref "IC4") (pin "13") (pinfunction "~{PWR2}_13") (pintype "output"))
    )
    (net (code "171") (name "unconnected-(IC5-PB0-Pad14)") (class "Default")
      (node (ref "IC5") (pin "14") (pinfunction "PB0_14") (pintype "bidirectional"))
    )
    (net (code "172") (name "unconnected-(IC5-PB4-Pad18)") (class "Default")
      (node (ref "IC5") (pin "18") (pinfunction "PB4_18") (pintype "bidirectional"))
    )
    (net (code "173") (name "unconnected-(IC5-PB5-Pad19)") (class "Default")
      (node (ref "IC5") (pin "19") (pinfunction "PB5_19") (pintype "bidirectional"))
    )
    (net (code "174") (name "unconnected-(IC5-PB6-Pad20)") (class "Default")
      (node (ref "IC5") (pin "20") (pinfunction "PB6_20") (pintype "bidirectional"))
    )
    (net (code "175") (name "unconnected-(IC5-PB7-Pad21)") (class "Default")
      (node (ref "IC5") (pin "21") (pinfunction "PB7_21") (pintype "bidirectional"))
    )
    (net (code "176") (name "unconnected-(IC5-PC2-Pad5)") (class "Default")
      (node (ref "IC5") (pin "5") (pinfunction "PC2_5") (pintype "bidirectional"))
    )
    (net (code "177") (name "unconnected-(IC5-PC4-Pad26)") (class "Default")
      (node (ref "IC5") (pin "26") (pinfunction "PC4_26") (pintype "bidirectional"))
    )
    (net (code "178") (name "unconnected-(IC5-PC5-Pad25)") (class "Default")
      (node (ref "IC5") (pin "25") (pinfunction "PC5_25") (pintype "bidirectional"))
    )
    (net (code "179") (name "unconnected-(IC5-PC6-Pad23)") (class "Default")
      (node (ref "IC5") (pin "23") (pinfunction "PC6_23") (pintype "bidirectional"))
    )
    (net (code "180") (name "unconnected-(IC5-PC7-Pad22)") (class "Default")
      (node (ref "IC5") (pin "22") (pinfunction "PC7_22") (pintype "bidirectional"))
    )
    (net (code "181") (name "unconnected-(IC5-PD0-Pad6)") (class "Default")
      (node (ref "IC5") (pin "6") (pinfunction "PD0_6") (pintype "bidirectional"))
    )
    (net (code "182") (name "unconnected-(IC5-PD1-Pad7)") (class "Default")
      (node (ref "IC5") (pin "7") (pinfunction "PD1_7") (pintype "bidirectional"))
    )
    (net (code "183") (name "unconnected-(IC5-PD6-Pad12)") (class "Default")
      (node (ref "IC5") (pin "12") (pinfunction "PD6_12") (pintype "bidirectional"))
    )
    (net (code "184") (name "unconnected-(IC6-NC{slash}FB-Pad4)") (class "Default")
      (node (ref "IC6") (pin "4") (pinfunction "NC/FB_4") (pintype "passive"))
    )
    (net (code "185") (name "unconnected-(IC9-COMP-Pad3)") (class "Default")
      (node (ref "IC9") (pin "3") (pinfunction "COMP_3") (pintype "bidirectional"))
    )
    (net (code "186") (name "unconnected-(J43-+-Pad1)") (class "Default")
      (node (ref "J43") (pin "1") (pinfunction "+_1") (pintype "bidirectional"))
    )
    (net (code "187") (name "unconnected-(Y3-STDBY-Pad1)") (class "Default")
      (node (ref "Y3") (pin "1") (pinfunction "STDBY_1") (pintype "bidirectional"))
    )
  )
)
